# io-board-f-b.net
KiCad netlist of a schematic drawn in EAGLE
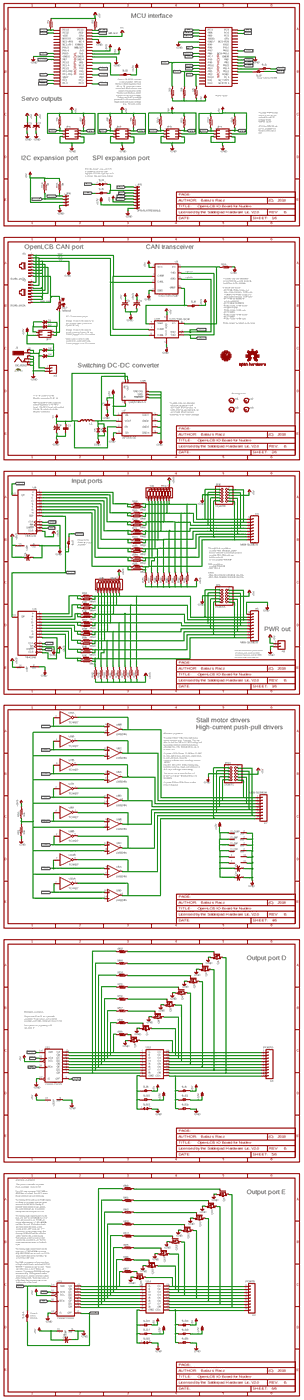
[diagram p0: schematic, sheet 1, overview]
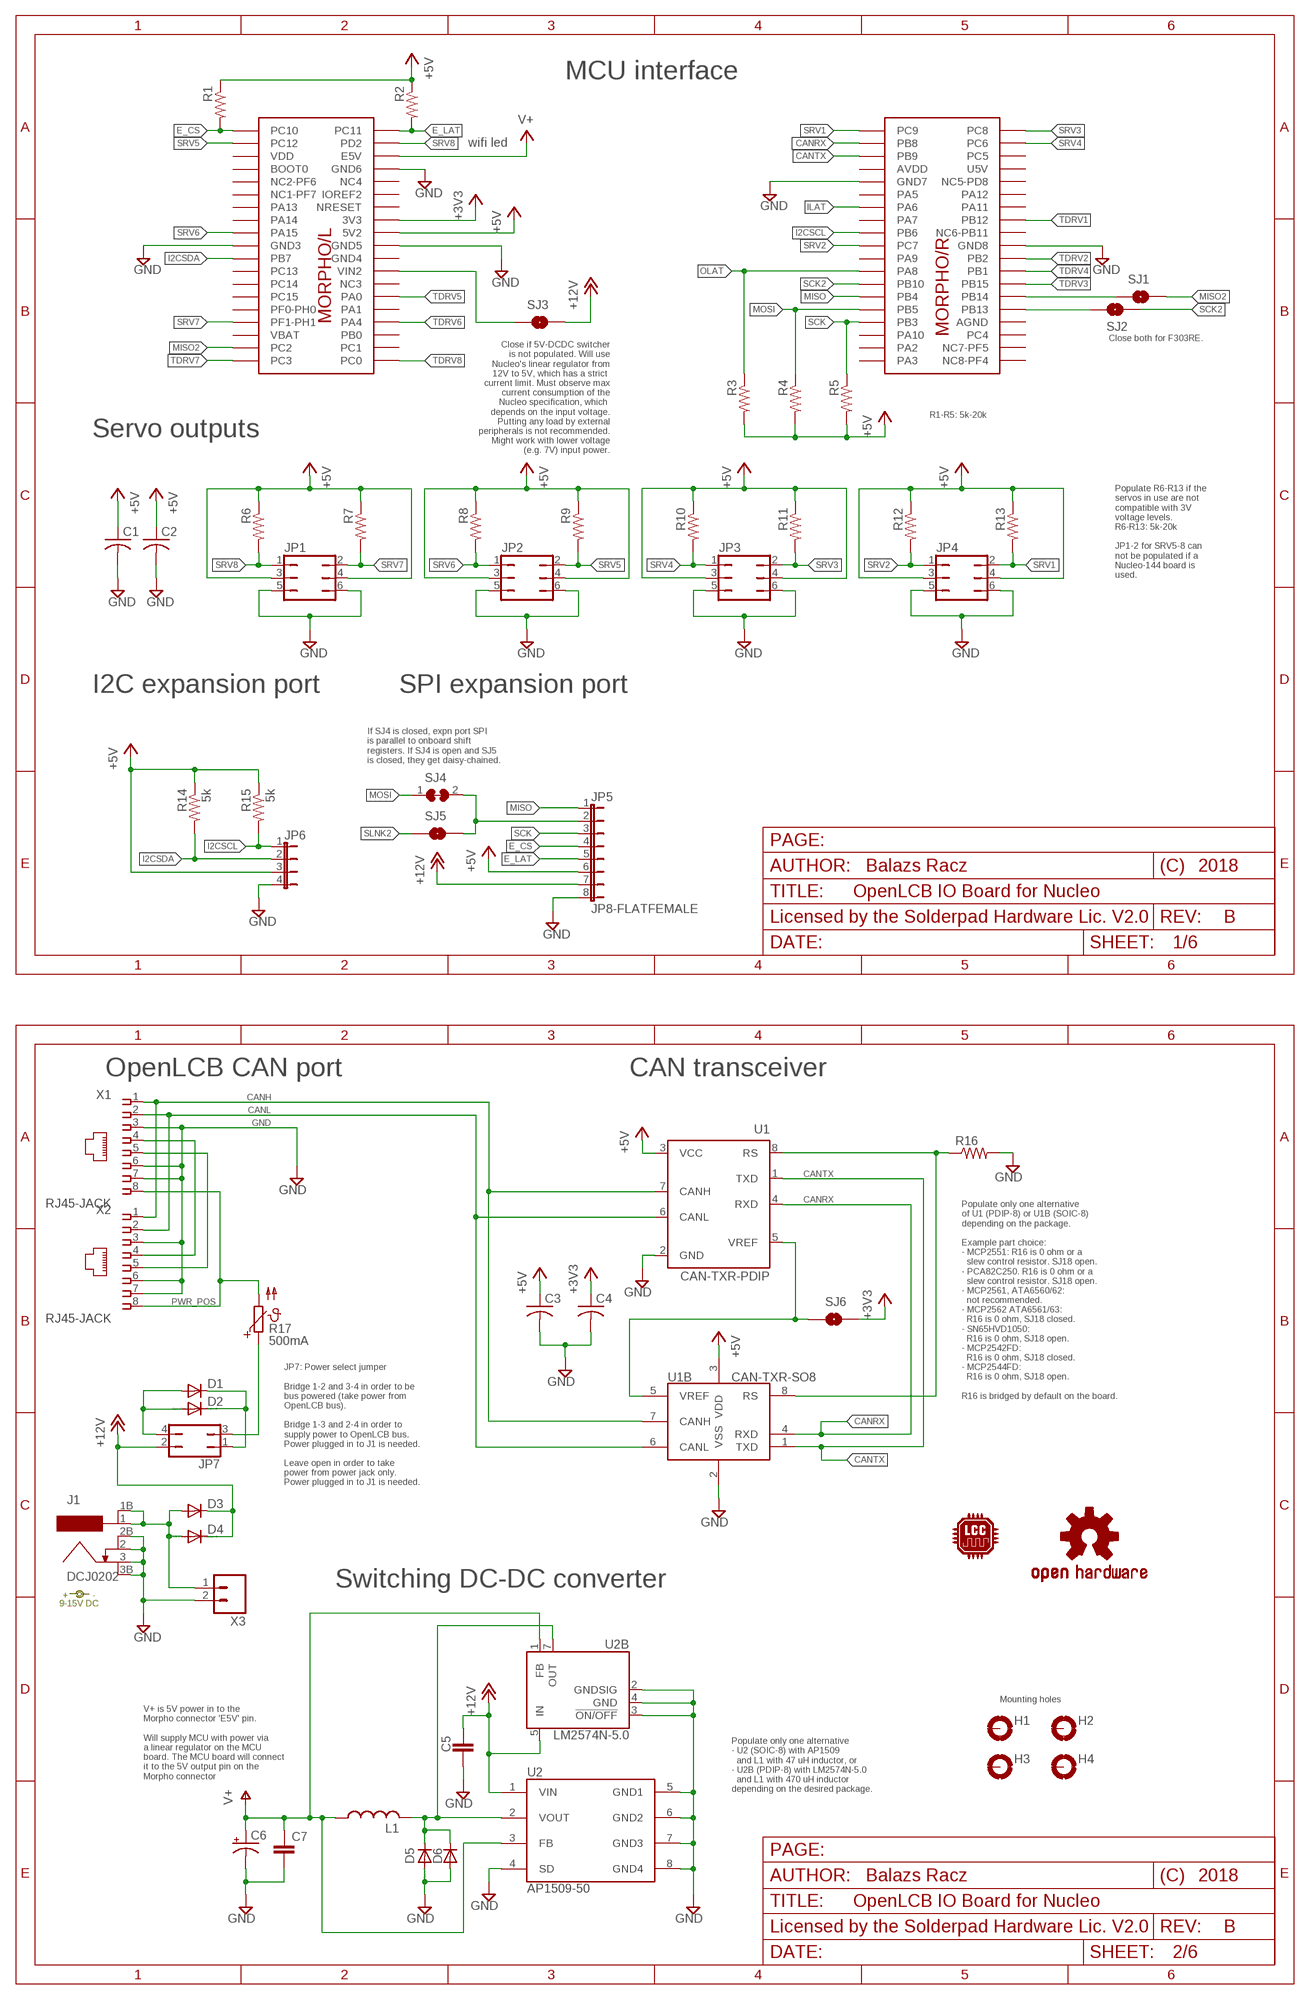
[diagram p1: schematic, sheet 1, part 1 of 4]
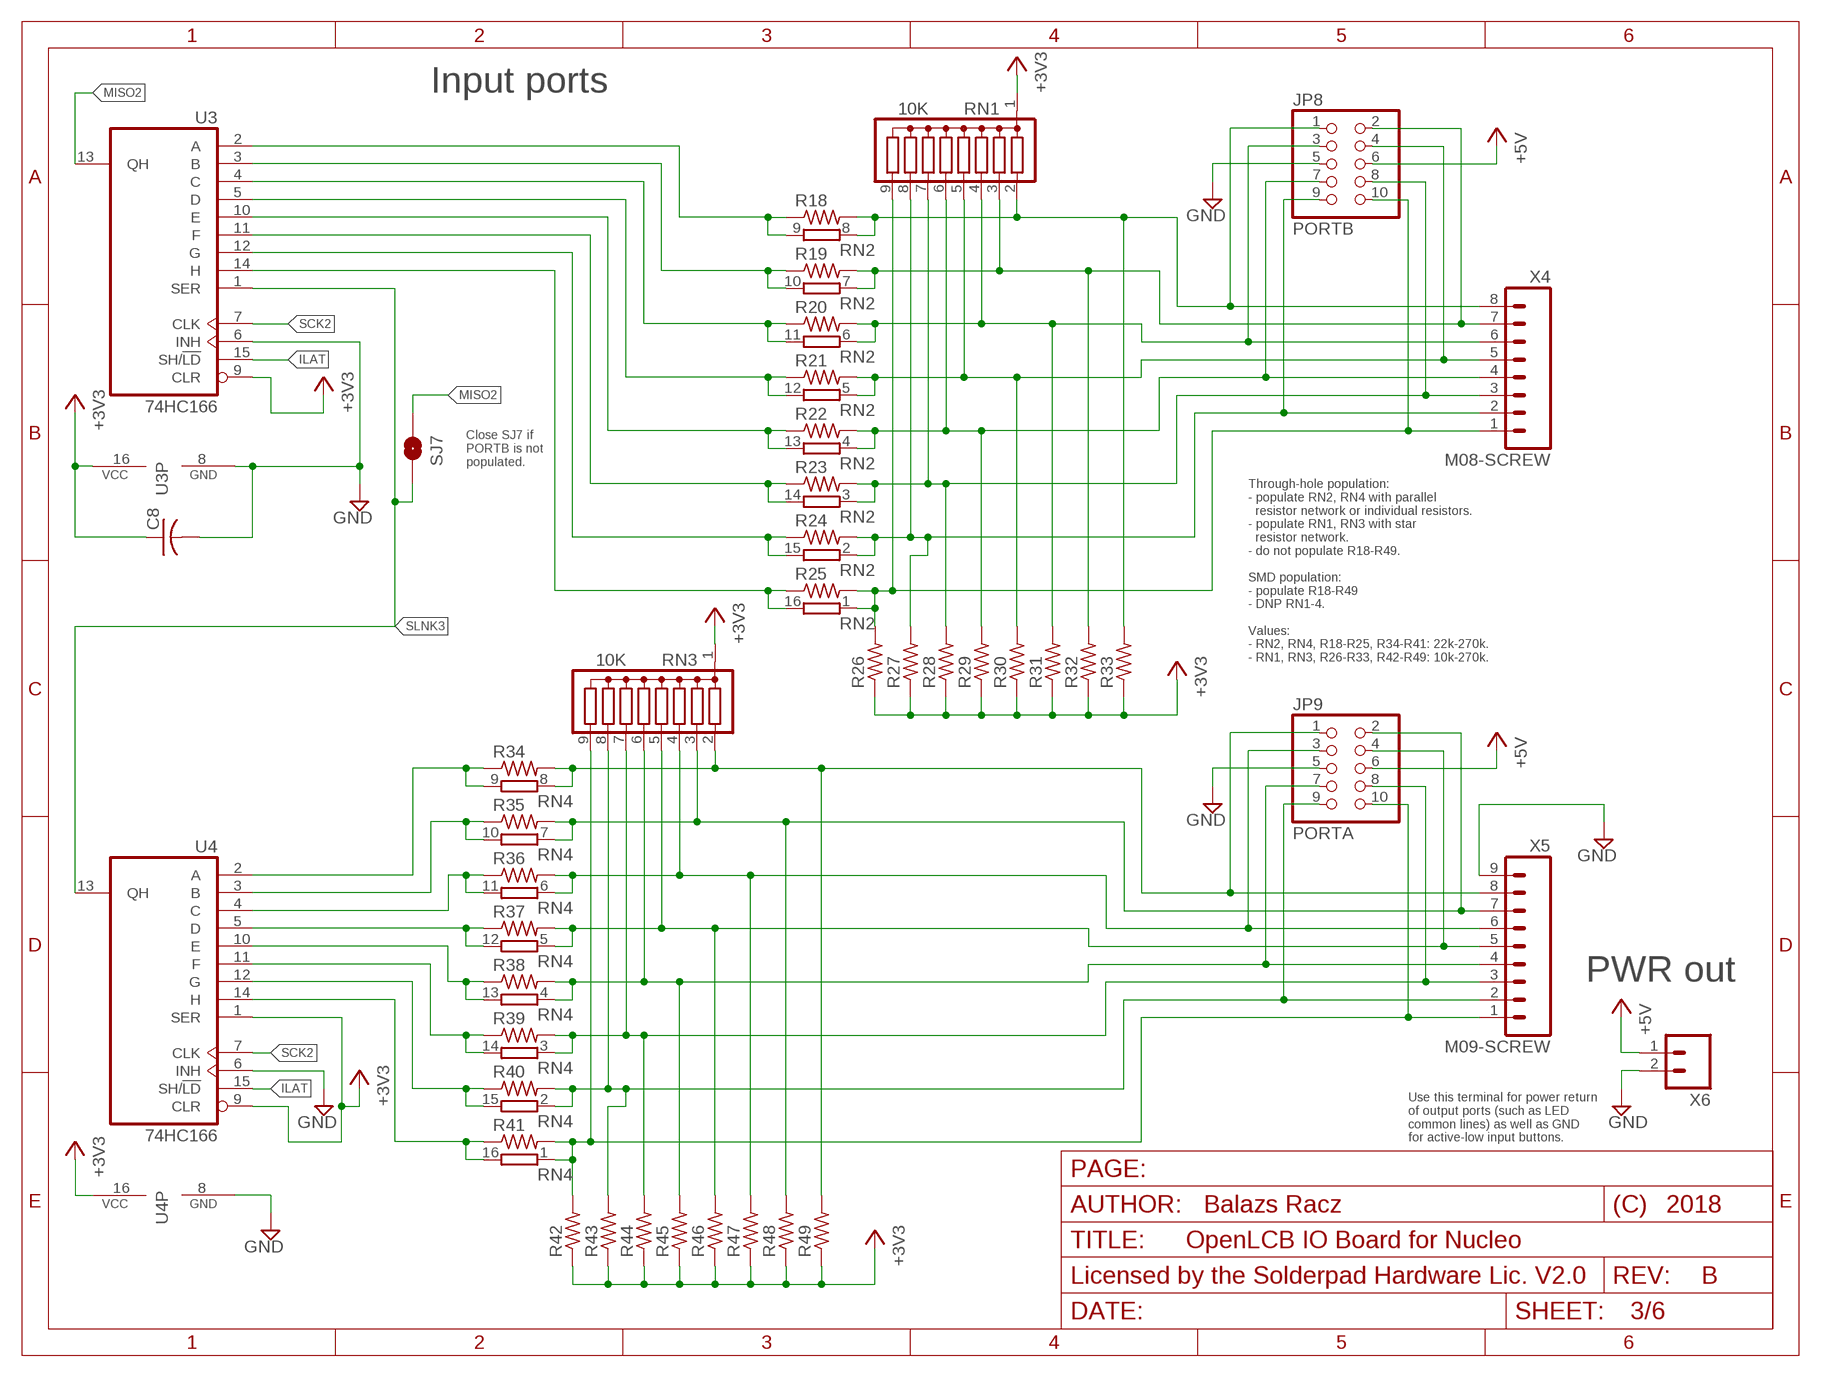
[diagram p2: schematic, sheet 1, part 2 of 4]
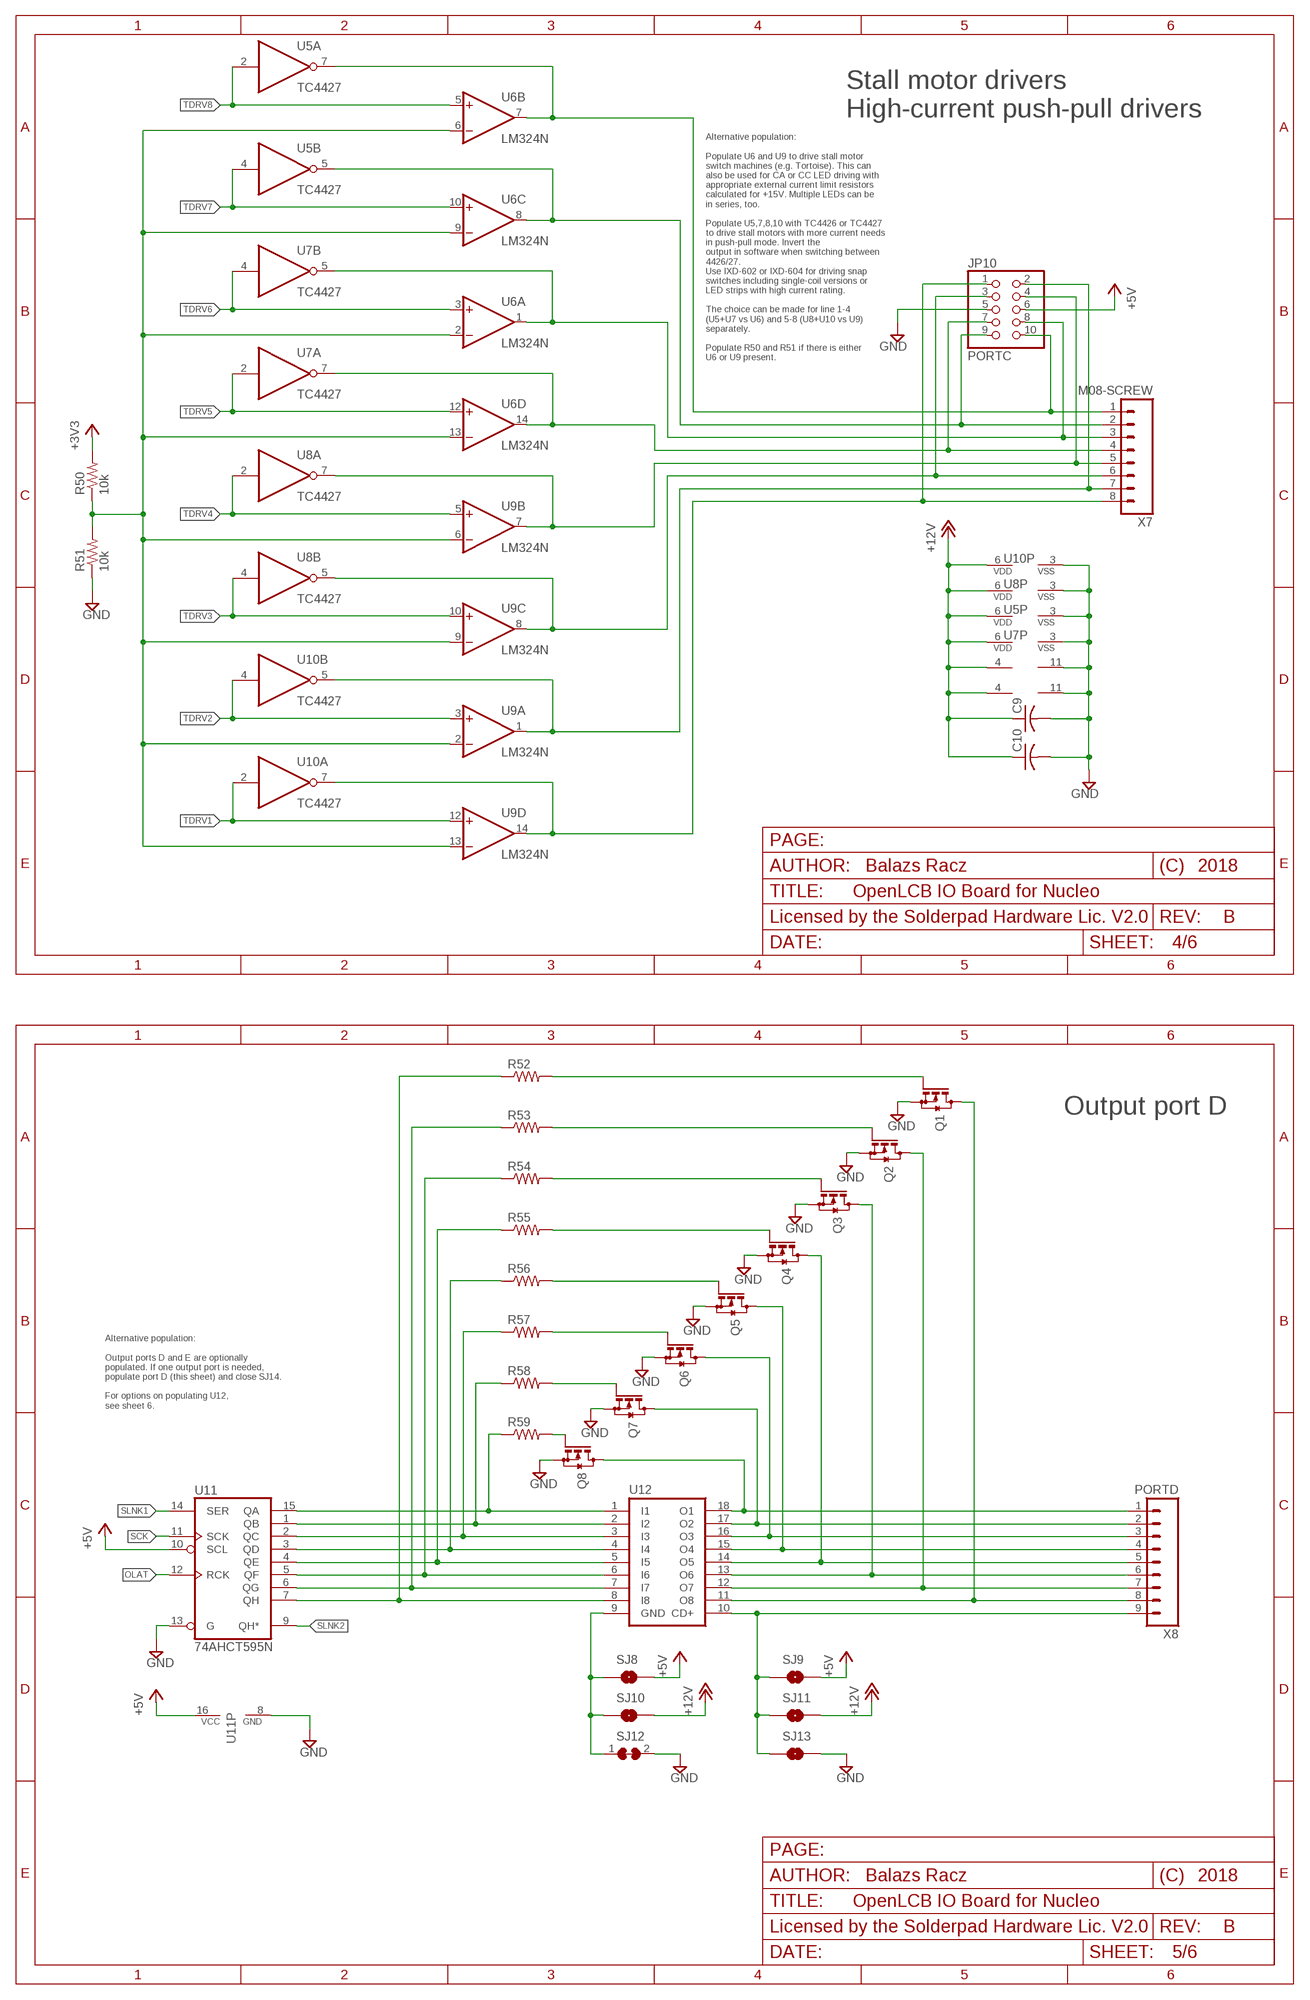
[diagram p3: schematic, sheet 1, part 3 of 4]
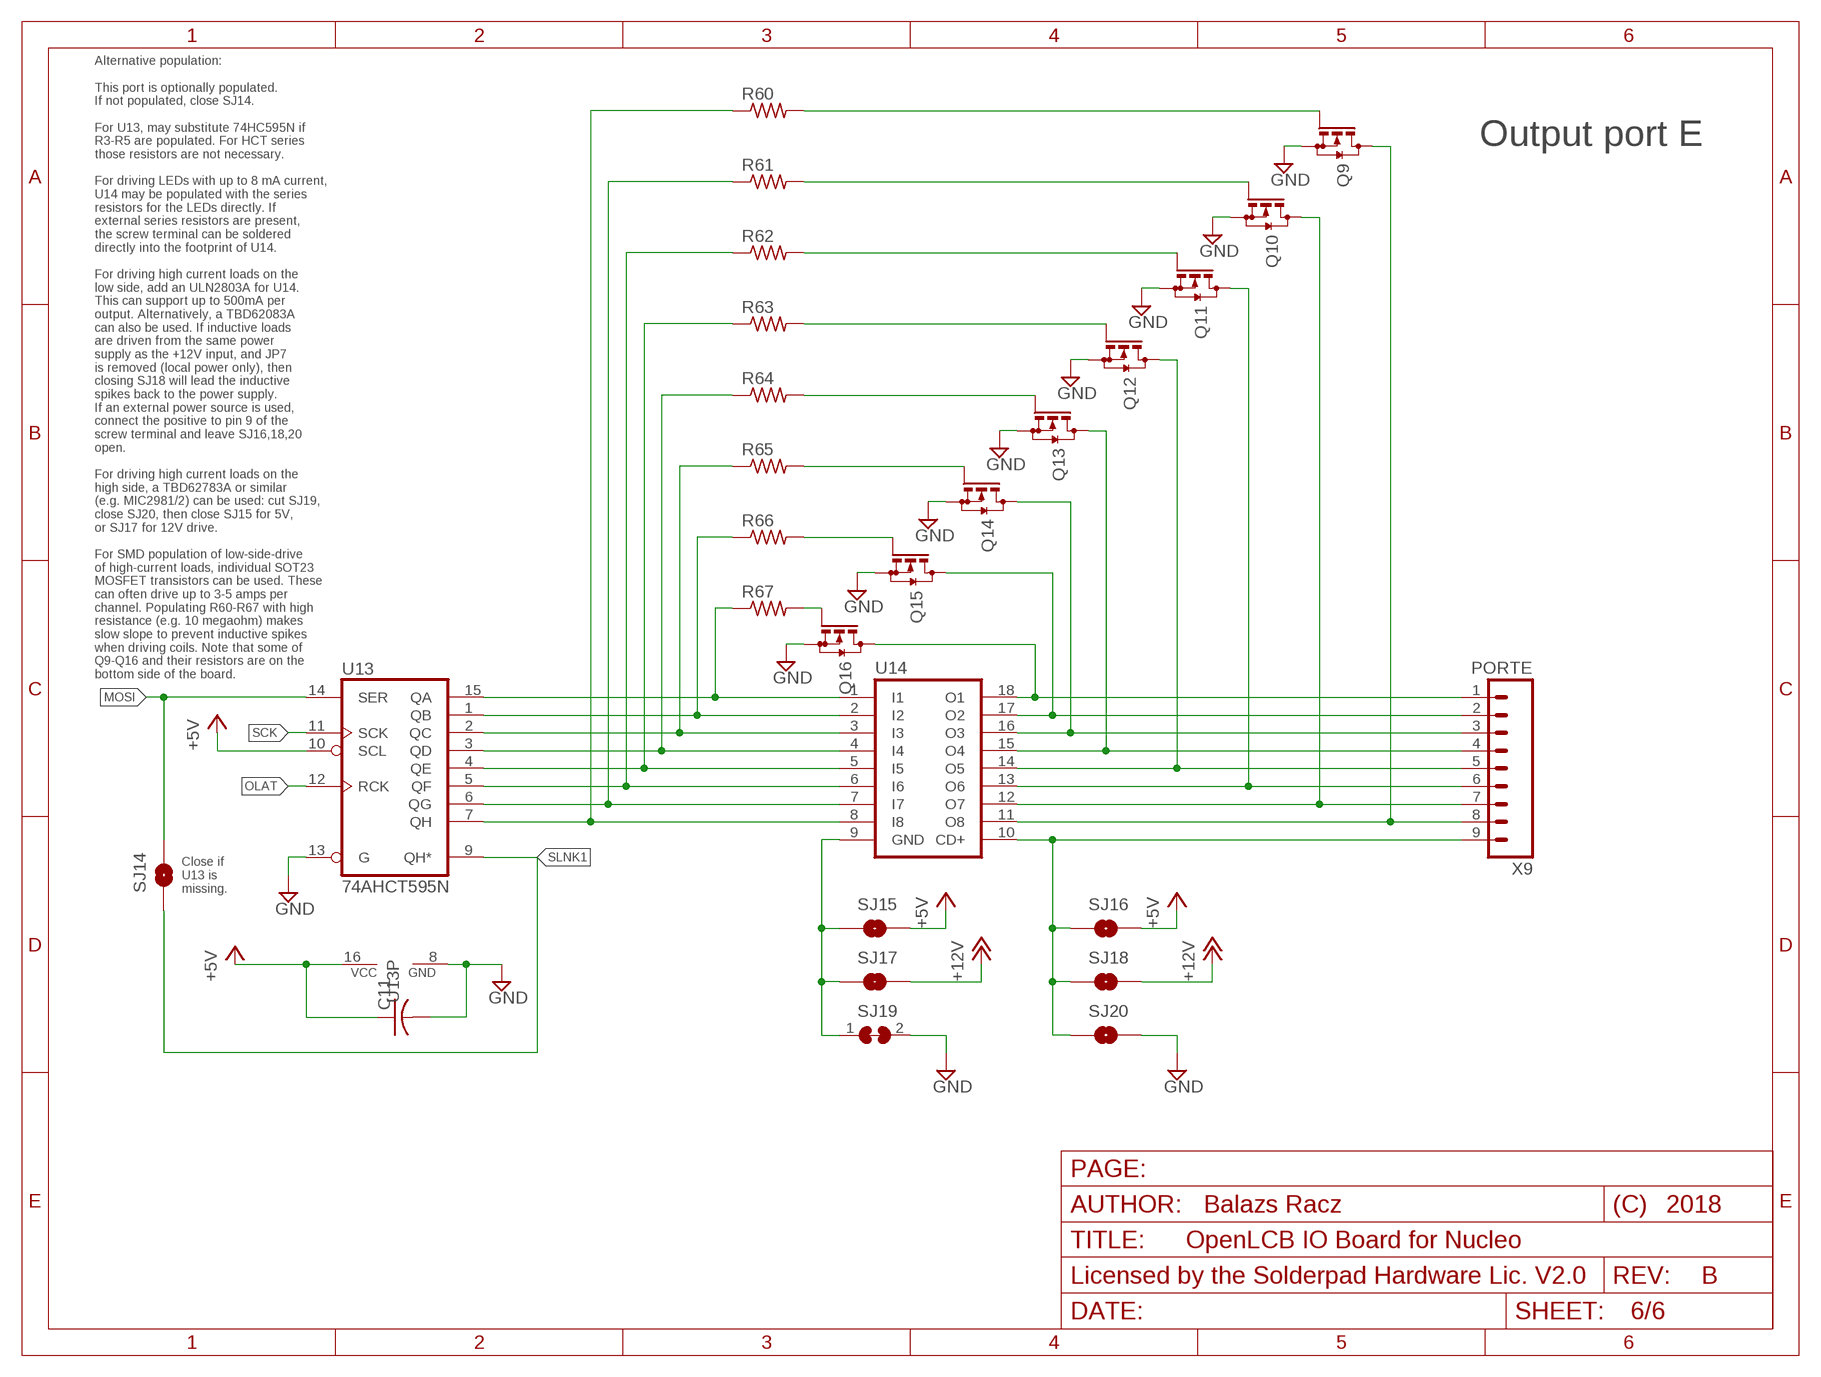
[diagram p4: schematic, sheet 1, part 4 of 4]

(export (version "E")
  (design (tool "Eeschema 10.0.6"))
  (components
    (comp (ref "C1")
      (value "C-USC1206")
      (footprint "eagle-import:C1206")
      (libsource (lib "eagle-import") (part "C-USC1206"))
    )
    (comp (ref "C2")
      (value "C-USC1206")
      (footprint "eagle-import:C1206")
      (libsource (lib "eagle-import") (part "C-USC1206"))
    )
    (comp (ref "C3")
      (value "C-USC0805")
      (footprint "eagle-import:C0805")
      (libsource (lib "eagle-import") (part "C-USC0805"))
    )
    (comp (ref "C4")
      (value "C-USC0805")
      (footprint "eagle-import:C0805")
      (libsource (lib "eagle-import") (part "C-USC0805"))
    )
    (comp (ref "C5")
      (value "C-EUC1206")
      (footprint "eagle-import:C1206")
      (libsource (lib "eagle-import") (part "C-EUC1206"))
    )
    (comp (ref "C6")
      (value "CPOL-USE2.5-5")
      (footprint "eagle-import:E2,5-5")
      (libsource (lib "eagle-import") (part "CPOL-USE2.5-5"))
    )
    (comp (ref "C7")
      (value "C-EUC1206")
      (footprint "eagle-import:C1206")
      (libsource (lib "eagle-import") (part "C-EUC1206"))
    )
    (comp (ref "C8")
      (value "C-USC0805")
      (footprint "eagle-import:C0805")
      (libsource (lib "eagle-import") (part "C-USC0805"))
    )
    (comp (ref "C9")
      (value "C-USC1206")
      (footprint "eagle-import:C1206")
      (libsource (lib "eagle-import") (part "C-USC1206"))
    )
    (comp (ref "C10")
      (value "C-USC1206")
      (footprint "eagle-import:C1206")
      (libsource (lib "eagle-import") (part "C-USC1206"))
    )
    (comp (ref "C11")
      (value "C-USC0805")
      (footprint "eagle-import:C0805")
      (libsource (lib "eagle-import") (part "C-USC0805"))
    )
    (comp (ref "D1")
      (value "DIODEDO-214AA-NODOC")
      (footprint "eagle-import:DO214AA-NODOC")
      (libsource (lib "eagle-import") (part "DIODEDO-214AA-NODOC"))
    )
    (comp (ref "D2")
      (value "DIODE-DO41-7.6")
      (footprint "eagle-import:DO41-7.6")
      (libsource (lib "eagle-import") (part "DIODE-DO41-7.6"))
    )
    (comp (ref "D3")
      (value "DIODEDO-214AA-NODOC")
      (footprint "eagle-import:DO214AA-NODOC")
      (libsource (lib "eagle-import") (part "DIODEDO-214AA-NODOC"))
    )
    (comp (ref "D4")
      (value "DIODE-DO41-7.6")
      (footprint "eagle-import:DO41-7.6")
      (libsource (lib "eagle-import") (part "DIODE-DO41-7.6"))
    )
    (comp (ref "D5")
      (value "DIODE-DO41-7.6")
      (footprint "eagle-import:DO41-7.6")
      (libsource (lib "eagle-import") (part "DIODE-DO41-7.6"))
    )
    (comp (ref "D6")
      (value "DIODEDO-214AA-NODOC")
      (footprint "eagle-import:DO214AA-NODOC")
      (libsource (lib "eagle-import") (part "DIODEDO-214AA-NODOC"))
    )
    (comp (ref "G1")
      (value "NUCLEO_64_GENERIC")
      (footprint "eagle-import:NUCLEO_BRD_BASE64")
      (libsource (lib "eagle-import") (part "NUCLEO_64_GENERIC"))
    )
    (comp (ref "H1")
      (value "MOUNT-PAD-ROUND3.3")
      (footprint "eagle-import:3,3-PAD")
      (libsource (lib "eagle-import") (part "MOUNT-PAD-ROUND3.3"))
    )
    (comp (ref "H2")
      (value "MOUNT-PAD-ROUND3.3")
      (footprint "eagle-import:3,3-PAD")
      (libsource (lib "eagle-import") (part "MOUNT-PAD-ROUND3.3"))
    )
    (comp (ref "H3")
      (value "MOUNT-PAD-ROUND3.3")
      (footprint "eagle-import:3,3-PAD")
      (libsource (lib "eagle-import") (part "MOUNT-PAD-ROUND3.3"))
    )
    (comp (ref "H4")
      (value "MOUNT-PAD-ROUND3.3")
      (footprint "eagle-import:3,3-PAD")
      (libsource (lib "eagle-import") (part "MOUNT-PAD-ROUND3.3"))
    )
    (comp (ref "J1")
      (value "DCJ0202")
      (footprint "eagle-import:DCJ0202")
      (libsource (lib "eagle-import") (part "DCJ0202"))
    )
    (comp (ref "JP1")
      (value "JP3Q")
      (footprint "eagle-import:JP3Q")
      (libsource (lib "eagle-import") (part "JP3Q"))
    )
    (comp (ref "JP2")
      (value "JP3Q")
      (footprint "eagle-import:JP3Q")
      (libsource (lib "eagle-import") (part "JP3Q"))
    )
    (comp (ref "JP3")
      (value "JP3Q")
      (footprint "eagle-import:JP3Q")
      (libsource (lib "eagle-import") (part "JP3Q"))
    )
    (comp (ref "JP4")
      (value "JP3Q")
      (footprint "eagle-import:JP3Q")
      (libsource (lib "eagle-import") (part "JP3Q"))
    )
    (comp (ref "JP5")
      (value "JP8-FLATFEMALE")
      (footprint "eagle-import:JP8F-FEM")
      (libsource (lib "eagle-import") (part "JP8-FLATFEMALE"))
    )
    (comp (ref "JP6")
      (value "JP4-FLAT")
      (footprint "eagle-import:JP4F")
      (libsource (lib "eagle-import") (part "JP4-FLAT"))
    )
    (comp (ref "JP7")
      (value "JP2Q")
      (footprint "eagle-import:JP2Q")
      (libsource (lib "eagle-import") (part "JP2Q"))
    )
    (comp (ref "JP8")
      (value "PORTB")
      (footprint "eagle-import:CON10M")
      (libsource (lib "eagle-import") (part "PINHD-2X5CN"))
    )
    (comp (ref "JP9")
      (value "PORTA")
      (footprint "eagle-import:CON10M")
      (libsource (lib "eagle-import") (part "PINHD-2X5CN"))
    )
    (comp (ref "JP10")
      (value "PORTC")
      (footprint "eagle-import:CON10M")
      (libsource (lib "eagle-import") (part "PINHD-2X5CN"))
    )
    (comp (ref "L1")
      (value "L-US")
      (footprint "eagle-import:L5-8,5")
      (libsource (lib "eagle-import") (part "L-US"))
    )
    (comp (ref "LG1")
      (value "LCC_LOGO")
      (footprint "eagle-import:LCC_LOGO")
      (libsource (lib "eagle-import") (part "LCC_LOGO"))
    )
    (comp (ref "LOGO1")
      (value "DOC-OSHW-LOGOM")
      (footprint "eagle-import:OSHW-LOGO-M")
      (libsource (lib "eagle-import") (part "DOC-OSHW-LOGOM"))
    )
    (comp (ref "P1")
      (value "9-15V DC")
      (footprint "eagle-import:POWER_USAGE")
      (libsource (lib "eagle-import") (part "DOC-POWER_LABEL"))
    )
    (comp (ref "Q1")
      (value "BSS123")
      (footprint "eagle-import:SOT23")
      (libsource (lib "eagle-import") (part "BSS123"))
    )
    (comp (ref "Q2")
      (value "BSS123")
      (footprint "eagle-import:SOT23")
      (libsource (lib "eagle-import") (part "BSS123"))
    )
    (comp (ref "Q3")
      (value "BSS123")
      (footprint "eagle-import:SOT23")
      (libsource (lib "eagle-import") (part "BSS123"))
    )
    (comp (ref "Q4")
      (value "BSS123")
      (footprint "eagle-import:SOT23")
      (libsource (lib "eagle-import") (part "BSS123"))
    )
    (comp (ref "Q5")
      (value "BSS123")
      (footprint "eagle-import:SOT23")
      (libsource (lib "eagle-import") (part "BSS123"))
    )
    (comp (ref "Q6")
      (value "BSS123")
      (footprint "eagle-import:SOT23")
      (libsource (lib "eagle-import") (part "BSS123"))
    )
    (comp (ref "Q7")
      (value "BSS123")
      (footprint "eagle-import:SOT23")
      (libsource (lib "eagle-import") (part "BSS123"))
    )
    (comp (ref "Q8")
      (value "BSS123")
      (footprint "eagle-import:SOT23")
      (libsource (lib "eagle-import") (part "BSS123"))
    )
    (comp (ref "Q9")
      (value "BSS123")
      (footprint "eagle-import:SOT23")
      (libsource (lib "eagle-import") (part "BSS123"))
    )
    (comp (ref "Q10")
      (value "BSS123")
      (footprint "eagle-import:SOT23")
      (libsource (lib "eagle-import") (part "BSS123"))
    )
    (comp (ref "Q11")
      (value "BSS123")
      (footprint "eagle-import:SOT23")
      (libsource (lib "eagle-import") (part "BSS123"))
    )
    (comp (ref "Q12")
      (value "BSS123")
      (footprint "eagle-import:SOT23")
      (libsource (lib "eagle-import") (part "BSS123"))
    )
    (comp (ref "Q13")
      (value "BSS123")
      (footprint "eagle-import:SOT23")
      (libsource (lib "eagle-import") (part "BSS123"))
    )
    (comp (ref "Q14")
      (value "BSS123")
      (footprint "eagle-import:SOT23")
      (libsource (lib "eagle-import") (part "BSS123"))
    )
    (comp (ref "Q15")
      (value "BSS123")
      (footprint "eagle-import:SOT23")
      (libsource (lib "eagle-import") (part "BSS123"))
    )
    (comp (ref "Q16")
      (value "BSS123")
      (footprint "eagle-import:SOT23")
      (libsource (lib "eagle-import") (part "BSS123"))
    )
    (comp (ref "R1")
      (value "R-US_R0805")
      (footprint "eagle-import:R0805")
      (libsource (lib "eagle-import") (part "rcl_334_R-US_R0805"))
    )
    (comp (ref "R2")
      (value "R-US_R0805")
      (footprint "eagle-import:R0805")
      (libsource (lib "eagle-import") (part "rcl_334_R-US_R0805"))
    )
    (comp (ref "R3")
      (value "R-US_R0805")
      (footprint "eagle-import:R0805")
      (libsource (lib "eagle-import") (part "rcl_334_R-US_R0805"))
    )
    (comp (ref "R4")
      (value "R-US_R0805")
      (footprint "eagle-import:R0805")
      (libsource (lib "eagle-import") (part "rcl_334_R-US_R0805"))
    )
    (comp (ref "R5")
      (value "R-US_R0805")
      (footprint "eagle-import:R0805")
      (libsource (lib "eagle-import") (part "rcl_334_R-US_R0805"))
    )
    (comp (ref "R6")
      (value "R-US_R0805")
      (footprint "eagle-import:R0805")
      (libsource (lib "eagle-import") (part "rcl_334_R-US_R0805"))
    )
    (comp (ref "R7")
      (value "R-US_R0805")
      (footprint "eagle-import:R0805")
      (libsource (lib "eagle-import") (part "rcl_334_R-US_R0805"))
    )
    (comp (ref "R8")
      (value "R-US_R0805")
      (footprint "eagle-import:R0805")
      (libsource (lib "eagle-import") (part "rcl_334_R-US_R0805"))
    )
    (comp (ref "R9")
      (value "R-US_R0805")
      (footprint "eagle-import:R0805")
      (libsource (lib "eagle-import") (part "rcl_334_R-US_R0805"))
    )
    (comp (ref "R10")
      (value "R-US_R0805")
      (footprint "eagle-import:R0805")
      (libsource (lib "eagle-import") (part "rcl_334_R-US_R0805"))
    )
    (comp (ref "R11")
      (value "R-US_R0805")
      (footprint "eagle-import:R0805")
      (libsource (lib "eagle-import") (part "rcl_334_R-US_R0805"))
    )
    (comp (ref "R12")
      (value "R-US_R0805")
      (footprint "eagle-import:R0805")
      (libsource (lib "eagle-import") (part "rcl_334_R-US_R0805"))
    )
    (comp (ref "R13")
      (value "R-US_R0805")
      (footprint "eagle-import:R0805")
      (libsource (lib "eagle-import") (part "rcl_334_R-US_R0805"))
    )
    (comp (ref "R14")
      (value "5k")
      (footprint "eagle-import:R0805")
      (libsource (lib "eagle-import") (part "rcl_334_R-US_R0805"))
    )
    (comp (ref "R15")
      (value "5k")
      (footprint "eagle-import:R0805")
      (libsource (lib "eagle-import") (part "rcl_334_R-US_R0805"))
    )
    (comp (ref "R16")
      (value "R-US_R0805")
      (footprint "eagle-import:R0805")
      (libsource (lib "eagle-import") (part "rcl_334_R-US_R0805"))
    )
    (comp (ref "R17")
      (value "500mA")
      (footprint "eagle-import:PTC1812")
      (libsource (lib "eagle-import") (part "PTC_1812"))
    )
    (comp (ref "R18")
      (value "R-US_R0603")
      (footprint "eagle-import:R0603")
      (libsource (lib "eagle-import") (part "rcl_334_R-US_R0603"))
    )
    (comp (ref "R19")
      (value "R-US_R0603")
      (footprint "eagle-import:R0603")
      (libsource (lib "eagle-import") (part "rcl_334_R-US_R0603"))
    )
    (comp (ref "R20")
      (value "R-US_R0603")
      (footprint "eagle-import:R0603")
      (libsource (lib "eagle-import") (part "rcl_334_R-US_R0603"))
    )
    (comp (ref "R21")
      (value "R-US_R0603")
      (footprint "eagle-import:R0603")
      (libsource (lib "eagle-import") (part "rcl_334_R-US_R0603"))
    )
    (comp (ref "R22")
      (value "R-US_R0603")
      (footprint "eagle-import:R0603")
      (libsource (lib "eagle-import") (part "rcl_334_R-US_R0603"))
    )
    (comp (ref "R23")
      (value "R-US_R0603")
      (footprint "eagle-import:R0603")
      (libsource (lib "eagle-import") (part "rcl_334_R-US_R0603"))
    )
    (comp (ref "R24")
      (value "R-US_R0603")
      (footprint "eagle-import:R0603")
      (libsource (lib "eagle-import") (part "rcl_334_R-US_R0603"))
    )
    (comp (ref "R25")
      (value "R-US_R0603")
      (footprint "eagle-import:R0603")
      (libsource (lib "eagle-import") (part "rcl_334_R-US_R0603"))
    )
    (comp (ref "R26")
      (value "R-US")
      (footprint "eagle-import:R0603")
      (libsource (lib "eagle-import") (part "R-US"))
    )
    (comp (ref "R27")
      (value "R-US")
      (footprint "eagle-import:R0603")
      (libsource (lib "eagle-import") (part "R-US"))
    )
    (comp (ref "R28")
      (value "R-US")
      (footprint "eagle-import:R0603")
      (libsource (lib "eagle-import") (part "R-US"))
    )
    (comp (ref "R29")
      (value "R-US")
      (footprint "eagle-import:R0603")
      (libsource (lib "eagle-import") (part "R-US"))
    )
    (comp (ref "R30")
      (value "R-US")
      (footprint "eagle-import:R0603")
      (libsource (lib "eagle-import") (part "R-US"))
    )
    (comp (ref "R31")
      (value "R-US")
      (footprint "eagle-import:R0603")
      (libsource (lib "eagle-import") (part "R-US"))
    )
    (comp (ref "R32")
      (value "R-US")
      (footprint "eagle-import:R0603")
      (libsource (lib "eagle-import") (part "R-US"))
    )
    (comp (ref "R33")
      (value "R-US")
      (footprint "eagle-import:R0603")
      (libsource (lib "eagle-import") (part "R-US"))
    )
    (comp (ref "R34")
      (value "R-US_R0603")
      (footprint "eagle-import:R0603")
      (libsource (lib "eagle-import") (part "rcl_334_R-US_R0603"))
    )
    (comp (ref "R35")
      (value "R-US_R0603")
      (footprint "eagle-import:R0603")
      (libsource (lib "eagle-import") (part "rcl_334_R-US_R0603"))
    )
    (comp (ref "R36")
      (value "R-US_R0603")
      (footprint "eagle-import:R0603")
      (libsource (lib "eagle-import") (part "rcl_334_R-US_R0603"))
    )
    (comp (ref "R37")
      (value "R-US_R0603")
      (footprint "eagle-import:R0603")
      (libsource (lib "eagle-import") (part "rcl_334_R-US_R0603"))
    )
    (comp (ref "R38")
      (value "R-US_R0603")
      (footprint "eagle-import:R0603")
      (libsource (lib "eagle-import") (part "rcl_334_R-US_R0603"))
    )
    (comp (ref "R39")
      (value "R-US_R0603")
      (footprint "eagle-import:R0603")
      (libsource (lib "eagle-import") (part "rcl_334_R-US_R0603"))
    )
    (comp (ref "R40")
      (value "R-US_R0603")
      (footprint "eagle-import:R0603")
      (libsource (lib "eagle-import") (part "rcl_334_R-US_R0603"))
    )
    (comp (ref "R41")
      (value "R-US_R0603")
      (footprint "eagle-import:R0603")
      (libsource (lib "eagle-import") (part "rcl_334_R-US_R0603"))
    )
    (comp (ref "R42")
      (value "R-US")
      (footprint "eagle-import:R0603")
      (libsource (lib "eagle-import") (part "R-US"))
    )
    (comp (ref "R43")
      (value "R-US")
      (footprint "eagle-import:R0603")
      (libsource (lib "eagle-import") (part "R-US"))
    )
    (comp (ref "R44")
      (value "R-US")
      (footprint "eagle-import:R0603")
      (libsource (lib "eagle-import") (part "R-US"))
    )
    (comp (ref "R45")
      (value "R-US")
      (footprint "eagle-import:R0603")
      (libsource (lib "eagle-import") (part "R-US"))
    )
    (comp (ref "R46")
      (value "R-US")
      (footprint "eagle-import:R0603")
      (libsource (lib "eagle-import") (part "R-US"))
    )
    (comp (ref "R47")
      (value "R-US")
      (footprint "eagle-import:R0603")
      (libsource (lib "eagle-import") (part "R-US"))
    )
    (comp (ref "R48")
      (value "R-US")
      (footprint "eagle-import:R0603")
      (libsource (lib "eagle-import") (part "R-US"))
    )
    (comp (ref "R49")
      (value "R-US")
      (footprint "eagle-import:R0603")
      (libsource (lib "eagle-import") (part "R-US"))
    )
    (comp (ref "R50")
      (value "10k")
      (footprint "eagle-import:R0805")
      (libsource (lib "eagle-import") (part "R-US_R0805"))
    )
    (comp (ref "R51")
      (value "10k")
      (footprint "eagle-import:R0805")
      (libsource (lib "eagle-import") (part "R-US_R0805"))
    )
    (comp (ref "R52")
      (value "R-US_R0603")
      (footprint "eagle-import:R0603")
      (libsource (lib "eagle-import") (part "R-US_R0603"))
    )
    (comp (ref "R53")
      (value "R-US_R0603")
      (footprint "eagle-import:R0603")
      (libsource (lib "eagle-import") (part "R-US_R0603"))
    )
    (comp (ref "R54")
      (value "R-US_R0603")
      (footprint "eagle-import:R0603")
      (libsource (lib "eagle-import") (part "R-US_R0603"))
    )
    (comp (ref "R55")
      (value "R-US_R0603")
      (footprint "eagle-import:R0603")
      (libsource (lib "eagle-import") (part "R-US_R0603"))
    )
    (comp (ref "R56")
      (value "R-US_R0603")
      (footprint "eagle-import:R0603")
      (libsource (lib "eagle-import") (part "R-US_R0603"))
    )
    (comp (ref "R57")
      (value "R-US_R0603")
      (footprint "eagle-import:R0603")
      (libsource (lib "eagle-import") (part "R-US_R0603"))
    )
    (comp (ref "R58")
      (value "R-US_R0603")
      (footprint "eagle-import:R0603")
      (libsource (lib "eagle-import") (part "R-US_R0603"))
    )
    (comp (ref "R59")
      (value "R-US_R0603")
      (footprint "eagle-import:R0603")
      (libsource (lib "eagle-import") (part "R-US_R0603"))
    )
    (comp (ref "R60")
      (value "R-US_R0603")
      (footprint "eagle-import:R0603")
      (libsource (lib "eagle-import") (part "R-US_R0603"))
    )
    (comp (ref "R61")
      (value "R-US_R0603")
      (footprint "eagle-import:R0603")
      (libsource (lib "eagle-import") (part "R-US_R0603"))
    )
    (comp (ref "R62")
      (value "R-US_R0603")
      (footprint "eagle-import:R0603")
      (libsource (lib "eagle-import") (part "R-US_R0603"))
    )
    (comp (ref "R63")
      (value "R-US_R0603")
      (footprint "eagle-import:R0603")
      (libsource (lib "eagle-import") (part "R-US_R0603"))
    )
    (comp (ref "R64")
      (value "R-US_R0603")
      (footprint "eagle-import:R0603")
      (libsource (lib "eagle-import") (part "R-US_R0603"))
    )
    (comp (ref "R65")
      (value "R-US_R0603")
      (footprint "eagle-import:R0603")
      (libsource (lib "eagle-import") (part "R-US_R0603"))
    )
    (comp (ref "R66")
      (value "R-US_R0603")
      (footprint "eagle-import:R0603")
      (libsource (lib "eagle-import") (part "R-US_R0603"))
    )
    (comp (ref "R67")
      (value "R-US_R0603")
      (footprint "eagle-import:R0603")
      (libsource (lib "eagle-import") (part "R-US_R0603"))
    )
    (comp (ref "RN1")
      (value "10K")
      (footprint "eagle-import:SIL9")
      (libsource (lib "eagle-import") (part "G08R"))
    )
    (comp (ref "RN2")
      (value "8R-P")
      (footprint "eagle-import:DIL16")
      (libsource (lib "eagle-import") (part "8R-P"))
    )
    (comp (ref "RN3")
      (value "10K")
      (footprint "eagle-import:SIL9")
      (libsource (lib "eagle-import") (part "G08R"))
    )
    (comp (ref "RN4")
      (value "8R-P")
      (footprint "eagle-import:DIL16")
      (libsource (lib "eagle-import") (part "8R-P"))
    )
    (comp (ref "SJ1")
      (value "SJRND2")
      (footprint "eagle-import:SJ_RND2")
      (libsource (lib "eagle-import") (part "SJRND2"))
    )
    (comp (ref "SJ2")
      (value "SJRND2")
      (footprint "eagle-import:SJ_RND2")
      (libsource (lib "eagle-import") (part "SJRND2"))
    )
    (comp (ref "SJ3")
      (value "SJRND2")
      (footprint "eagle-import:SJ_RND2")
      (libsource (lib "eagle-import") (part "SJRND2"))
    )
    (comp (ref "SJ4")
      (value "SJ-C")
      (footprint "eagle-import:SJW-C")
      (libsource (lib "eagle-import") (part "SJ-C"))
    )
    (comp (ref "SJ5")
      (value "SJRND2")
      (footprint "eagle-import:SJ_RND2")
      (libsource (lib "eagle-import") (part "SJRND2"))
    )
    (comp (ref "SJ6")
      (value "SJRND2")
      (footprint "eagle-import:SJ_RND2")
      (libsource (lib "eagle-import") (part "SJRND2"))
    )
    (comp (ref "SJ7")
      (value "SJRND2")
      (footprint "eagle-import:SJ_RND2")
      (libsource (lib "eagle-import") (part "SJRND2"))
    )
    (comp (ref "SJ8")
      (value "SJRND2")
      (footprint "eagle-import:SJ_RND2")
      (libsource (lib "eagle-import") (part "SJRND2"))
    )
    (comp (ref "SJ9")
      (value "SJRND2")
      (footprint "eagle-import:SJ_RND2")
      (libsource (lib "eagle-import") (part "SJRND2"))
    )
    (comp (ref "SJ10")
      (value "SJRND2")
      (footprint "eagle-import:SJ_RND2")
      (libsource (lib "eagle-import") (part "SJRND2"))
    )
    (comp (ref "SJ11")
      (value "SJRND2")
      (footprint "eagle-import:SJ_RND2")
      (libsource (lib "eagle-import") (part "SJRND2"))
    )
    (comp (ref "SJ12")
      (value "SJ-C")
      (footprint "eagle-import:SJW-C")
      (libsource (lib "eagle-import") (part "SJ-C"))
    )
    (comp (ref "SJ13")
      (value "SJRND2")
      (footprint "eagle-import:SJ_RND2")
      (libsource (lib "eagle-import") (part "SJRND2"))
    )
    (comp (ref "SJ14")
      (value "SJRND2")
      (footprint "eagle-import:SJ_RND2")
      (libsource (lib "eagle-import") (part "SJRND2"))
    )
    (comp (ref "SJ15")
      (value "SJRND2")
      (footprint "eagle-import:SJ_RND2")
      (libsource (lib "eagle-import") (part "SJRND2"))
    )
    (comp (ref "SJ16")
      (value "SJRND2")
      (footprint "eagle-import:SJ_RND2")
      (libsource (lib "eagle-import") (part "SJRND2"))
    )
    (comp (ref "SJ17")
      (value "SJRND2")
      (footprint "eagle-import:SJ_RND2")
      (libsource (lib "eagle-import") (part "SJRND2"))
    )
    (comp (ref "SJ18")
      (value "SJRND2")
      (footprint "eagle-import:SJ_RND2")
      (libsource (lib "eagle-import") (part "SJRND2"))
    )
    (comp (ref "SJ19")
      (value "SJ-C")
      (footprint "eagle-import:SJW-C")
      (libsource (lib "eagle-import") (part "SJ-C"))
    )
    (comp (ref "SJ20")
      (value "SJRND2")
      (footprint "eagle-import:SJ_RND2")
      (libsource (lib "eagle-import") (part "SJRND2"))
    )
    (comp (ref "U1")
      (value "CAN-TXR-PDIP")
      (footprint "eagle-import:DIL08")
      (libsource (lib "eagle-import") (part "PCA82C250"))
    )
    (comp (ref "U1B")
      (value "CAN-TXR-SO8")
      (footprint "eagle-import:SO-08")
      (libsource (lib "eagle-import") (part "MCP2551-SN"))
    )
    (comp (ref "U2")
      (value "AP1509-50")
      (footprint "eagle-import:SO-08")
      (libsource (lib "eagle-import") (part "AP1509"))
    )
    (comp (ref "U2B")
      (value "LM2574N-5.0")
      (footprint "eagle-import:DIL08")
      (libsource (lib "eagle-import") (part "LM2574?-N5.0"))
    )
    (comp (ref "U3")
      (value "74HC166")
      (footprint "eagle-import:DIL16")
      (libsource (lib "eagle-import") (part "74166N"))
    )
    (comp (ref "U4")
      (value "74HC166")
      (footprint "eagle-import:DIL16")
      (libsource (lib "eagle-import") (part "74166N"))
    )
    (comp (ref "U5")
      (value "TC4427")
      (footprint "eagle-import:DIL08-LONG")
      (libsource (lib "eagle-import") (part "TC4426APDIP"))
    )
    (comp (ref "U6")
      (value "LM324N")
      (footprint "eagle-import:DIL14")
      (libsource (lib "eagle-import") (part "LM324N"))
    )
    (comp (ref "U7")
      (value "TC4427")
      (footprint "eagle-import:DIL08-LONG")
      (libsource (lib "eagle-import") (part "TC4426APDIP"))
    )
    (comp (ref "U8")
      (value "TC4427")
      (footprint "eagle-import:DIL08-LONG")
      (libsource (lib "eagle-import") (part "TC4426APDIP"))
    )
    (comp (ref "U9")
      (value "LM324N")
      (footprint "eagle-import:DIL14")
      (libsource (lib "eagle-import") (part "LM324N"))
    )
    (comp (ref "U10")
      (value "TC4427")
      (footprint "eagle-import:DIL08-LONG")
      (libsource (lib "eagle-import") (part "TC4426APDIP"))
    )
    (comp (ref "U11")
      (value "74AHCT595N")
      (footprint "eagle-import:DIL16")
      (libsource (lib "eagle-import") (part "74595NHCT"))
    )
    (comp (ref "U12")
      (value "ULN2803A")
      (footprint "eagle-import:DIL18-THIN")
      (libsource (lib "eagle-import") (part "ULN2803A"))
    )
    (comp (ref "U13")
      (value "74AHCT595N")
      (footprint "eagle-import:DIL16")
      (libsource (lib "eagle-import") (part "74595NHCT"))
    )
    (comp (ref "U14")
      (value "ULN2803A")
      (footprint "eagle-import:DIL18-THIN")
      (libsource (lib "eagle-import") (part "ULN2803A"))
    )
    (comp (ref "X1")
      (value "RJ45-JACK")
      (footprint "eagle-import:RJ45-PULSE-E5J88")
      (libsource (lib "eagle-import") (part "RJ45-JACKRJ45-PULSE-E5J00"))
    )
    (comp (ref "X2")
      (value "RJ45-JACK")
      (footprint "eagle-import:RJ45-PULSE-E5J88")
      (libsource (lib "eagle-import") (part "RJ45-JACKRJ45-PULSE-E5J00"))
    )
    (comp (ref "X3")
      (value "CONNECTOR-M023.5MM-LOCK")
      (footprint "eagle-import:SCREWTERMINAL-3.5MM-2_LOCK")
      (libsource (lib "eagle-import") (part "CONNECTOR-M023.5MM-LOCK"))
    )
    (comp (ref "X4")
      (value "M08-SCREW")
      (footprint "eagle-import:1X08_TERMINAL")
      (libsource (lib "eagle-import") (part "M08-SCREW"))
    )
    (comp (ref "X5")
      (value "M09-SCREW")
      (footprint "eagle-import:1X09_TERMINAL")
      (libsource (lib "eagle-import") (part "M09-SCREW"))
    )
    (comp (ref "X6")
      (value "CONNECTOR-M023.5MM-LOCK")
      (footprint "eagle-import:SCREWTERMINAL-3.5MM-2_LOCK")
      (libsource (lib "eagle-import") (part "CONNECTOR-M023.5MM-LOCK"))
    )
    (comp (ref "X7")
      (value "M08-SCREW")
      (footprint "eagle-import:1X08_TERMINAL")
      (libsource (lib "eagle-import") (part "M08-SCREW"))
    )
    (comp (ref "X8")
      (value "PORTD")
      (footprint "eagle-import:1X09_TERMINAL")
      (libsource (lib "eagle-import") (part "M09-SCREW"))
    )
    (comp (ref "X9")
      (value "PORTE")
      (footprint "eagle-import:1X09_TERMINAL")
      (libsource (lib "eagle-import") (part "M09-SCREW"))
    )
  )
  (nets
    (net (code "1") (name "+3V3") (class "Default")
      (node (ref "C4") (pin "1") (pinfunction "1_1") (pintype "passive"))
      (node (ref "C8") (pin "1") (pinfunction "1_1") (pintype "passive"))
      (node (ref "G1") (pin "3V3") (pinfunction "3V3_3V3") (pintype "power_in"))
      (node (ref "R26") (pin "1") (pinfunction "1_1") (pintype "passive"))
      (node (ref "R27") (pin "1") (pinfunction "1_1") (pintype "passive"))
      (node (ref "R28") (pin "1") (pinfunction "1_1") (pintype "passive"))
      (node (ref "R29") (pin "1") (pinfunction "1_1") (pintype "passive"))
      (node (ref "R30") (pin "1") (pinfunction "1_1") (pintype "passive"))
      (node (ref "R31") (pin "1") (pinfunction "1_1") (pintype "passive"))
      (node (ref "R32") (pin "1") (pinfunction "1_1") (pintype "passive"))
      (node (ref "R33") (pin "1") (pinfunction "1_1") (pintype "passive"))
      (node (ref "R42") (pin "1") (pinfunction "1_1") (pintype "passive"))
      (node (ref "R43") (pin "1") (pinfunction "1_1") (pintype "passive"))
      (node (ref "R44") (pin "1") (pinfunction "1_1") (pintype "passive"))
      (node (ref "R45") (pin "1") (pinfunction "1_1") (pintype "passive"))
      (node (ref "R46") (pin "1") (pinfunction "1_1") (pintype "passive"))
      (node (ref "R47") (pin "1") (pinfunction "1_1") (pintype "passive"))
      (node (ref "R48") (pin "1") (pinfunction "1_1") (pintype "passive"))
      (node (ref "R49") (pin "1") (pinfunction "1_1") (pintype "passive"))
      (node (ref "R50") (pin "2") (pinfunction "2_2") (pintype "passive"))
      (node (ref "RN1") (pin "1") (pinfunction "1_1") (pintype "passive"))
      (node (ref "RN3") (pin "1") (pinfunction "1_1") (pintype "passive"))
      (node (ref "SJ6") (pin "P$1") (pinfunction "1_P$1") (pintype "passive"))
      (node (ref "U3") (pin "16") (pinfunction "VCC_16") (pintype "power_in"))
      (node (ref "U3") (pin "9") (pinfunction "CLR_9") (pintype "input"))
      (node (ref "U4") (pin "1") (pinfunction "SER_1") (pintype "input"))
      (node (ref "U4") (pin "16") (pinfunction "VCC_16") (pintype "power_in"))
      (node (ref "U4") (pin "9") (pinfunction "CLR_9") (pintype "input"))
    )
    (net (code "2") (name "+5V") (class "Default")
      (node (ref "C1") (pin "1") (pinfunction "1_1") (pintype "passive"))
      (node (ref "C11") (pin "1") (pinfunction "1_1") (pintype "passive"))
      (node (ref "C2") (pin "1") (pinfunction "1_1") (pintype "passive"))
      (node (ref "C3") (pin "1") (pinfunction "1_1") (pintype "passive"))
      (node (ref "G1") (pin "5V2") (pinfunction "5V2_5V2") (pintype "power_in"))
      (node (ref "JP1") (pin "3") (pinfunction "3_3") (pintype "passive"))
      (node (ref "JP1") (pin "4") (pinfunction "4_4") (pintype "passive"))
      (node (ref "JP10") (pin "6") (pinfunction "6_6") (pintype "passive"))
      (node (ref "JP2") (pin "3") (pinfunction "3_3") (pintype "passive"))
      (node (ref "JP2") (pin "4") (pinfunction "4_4") (pintype "passive"))
      (node (ref "JP3") (pin "3") (pinfunction "3_3") (pintype "passive"))
      (node (ref "JP3") (pin "4") (pinfunction "4_4") (pintype "passive"))
      (node (ref "JP4") (pin "3") (pinfunction "3_3") (pintype "passive"))
      (node (ref "JP4") (pin "4") (pinfunction "4_4") (pintype "passive"))
      (node (ref "JP5") (pin "6") (pinfunction "6_6") (pintype "passive"))
      (node (ref "JP6") (pin "3") (pinfunction "3_3") (pintype "passive"))
      (node (ref "JP8") (pin "6") (pinfunction "6_6") (pintype "passive"))
      (node (ref "JP9") (pin "6") (pinfunction "6_6") (pintype "passive"))
      (node (ref "R1") (pin "1") (pinfunction "1_1") (pintype "passive"))
      (node (ref "R10") (pin "1") (pinfunction "1_1") (pintype "passive"))
      (node (ref "R11") (pin "1") (pinfunction "1_1") (pintype "passive"))
      (node (ref "R12") (pin "1") (pinfunction "1_1") (pintype "passive"))
      (node (ref "R13") (pin "1") (pinfunction "1_1") (pintype "passive"))
      (node (ref "R14") (pin "1") (pinfunction "1_1") (pintype "passive"))
      (node (ref "R15") (pin "1") (pinfunction "1_1") (pintype "passive"))
      (node (ref "R2") (pin "1") (pinfunction "1_1") (pintype "passive"))
      (node (ref "R3") (pin "2") (pinfunction "2_2") (pintype "passive"))
      (node (ref "R4") (pin "2") (pinfunction "2_2") (pintype "passive"))
      (node (ref "R5") (pin "2") (pinfunction "2_2") (pintype "passive"))
      (node (ref "R6") (pin "1") (pinfunction "1_1") (pintype "passive"))
      (node (ref "R7") (pin "1") (pinfunction "1_1") (pintype "passive"))
      (node (ref "R8") (pin "1") (pinfunction "1_1") (pintype "passive"))
      (node (ref "R9") (pin "1") (pinfunction "1_1") (pintype "passive"))
      (node (ref "SJ15") (pin "P$2") (pinfunction "2_P$2") (pintype "passive"))
      (node (ref "SJ16") (pin "P$2") (pinfunction "2_P$2") (pintype "passive"))
      (node (ref "SJ8") (pin "P$2") (pinfunction "2_P$2") (pintype "passive"))
      (node (ref "SJ9") (pin "P$2") (pinfunction "2_P$2") (pintype "passive"))
      (node (ref "U1") (pin "3") (pinfunction "VCC_3") (pintype "power_in"))
      (node (ref "U11") (pin "10") (pinfunction "SCL_10") (pintype "input"))
      (node (ref "U11") (pin "16") (pinfunction "VCC_16") (pintype "power_in"))
      (node (ref "U13") (pin "10") (pinfunction "SCL_10") (pintype "input"))
      (node (ref "U13") (pin "16") (pinfunction "VCC_16") (pintype "power_in"))
      (node (ref "U1B") (pin "3") (pinfunction "VDD_3") (pintype "power_in"))
      (node (ref "X6") (pin "1") (pinfunction "1_1") (pintype "passive"))
    )
    (net (code "3") (name "+12V") (class "Default")
      (node (ref "C10") (pin "1") (pinfunction "1_1") (pintype "passive"))
      (node (ref "C5") (pin "1") (pinfunction "1_1") (pintype "passive"))
      (node (ref "C9") (pin "1") (pinfunction "1_1") (pintype "passive"))
      (node (ref "D3") (pin "C") (pinfunction "C_C") (pintype "passive"))
      (node (ref "D4") (pin "C") (pinfunction "C_C") (pintype "passive"))
      (node (ref "JP5") (pin "7") (pinfunction "7_7") (pintype "passive"))
      (node (ref "JP7") (pin "2") (pinfunction "2_2") (pintype "passive"))
      (node (ref "SJ10") (pin "P$2") (pinfunction "2_P$2") (pintype "passive"))
      (node (ref "SJ11") (pin "P$2") (pinfunction "2_P$2") (pintype "passive"))
      (node (ref "SJ17") (pin "P$2") (pinfunction "2_P$2") (pintype "passive"))
      (node (ref "SJ18") (pin "P$2") (pinfunction "2_P$2") (pintype "passive"))
      (node (ref "SJ3") (pin "P$2") (pinfunction "2_P$2") (pintype "passive"))
      (node (ref "U10") (pin "6") (pinfunction "VDD_6") (pintype "power_in"))
      (node (ref "U2") (pin "1") (pinfunction "VIN_1") (pintype "bidirectional"))
      (node (ref "U2B") (pin "5") (pinfunction "IN_5") (pintype "input"))
      (node (ref "U5") (pin "6") (pinfunction "VDD_6") (pintype "power_in"))
      (node (ref "U6") (pin "4") (pinfunction "V+_4") (pintype "power_in"))
      (node (ref "U7") (pin "6") (pinfunction "VDD_6") (pintype "power_in"))
      (node (ref "U8") (pin "6") (pinfunction "VDD_6") (pintype "power_in"))
      (node (ref "U9") (pin "4") (pinfunction "V+_4") (pintype "power_in"))
    )
    (net (code "4") (name "/AGND") (class "Default")
      (node (ref "G1") (pin "AGND") (pinfunction "AGND_AGND") (pintype "power_in"))
    )
    (net (code "5") (name "/AVDD") (class "Default")
      (node (ref "G1") (pin "AVDD") (pinfunction "AVDD_AVDD") (pintype "power_in"))
    )
    (net (code "6") (name "/CANH") (class "Default")
      (node (ref "U1") (pin "7") (pinfunction "CANH_7") (pintype "bidirectional"))
      (node (ref "U1B") (pin "7") (pinfunction "CANH_7") (pintype "bidirectional"))
      (node (ref "X1") (pin "1") (pinfunction "1_1") (pintype "passive"))
      (node (ref "X2") (pin "1") (pinfunction "1_1") (pintype "passive"))
    )
    (net (code "7") (name "/CANL") (class "Default")
      (node (ref "U1") (pin "6") (pinfunction "CANL_6") (pintype "bidirectional"))
      (node (ref "U1B") (pin "6") (pinfunction "CANL_6") (pintype "bidirectional"))
      (node (ref "X1") (pin "2") (pinfunction "2_2") (pintype "passive"))
      (node (ref "X2") (pin "2") (pinfunction "2_2") (pintype "passive"))
    )
    (net (code "8") (name "/GND4") (class "Default")
      (node (ref "G1") (pin "GND4") (pinfunction "GND4_GND4") (pintype "power_in"))
    )
    (net (code "9") (name "/PWR_POS") (class "Default")
      (node (ref "R17") (pin "2") (pinfunction "2_2") (pintype "passive"))
      (node (ref "X1") (pin "8") (pinfunction "8_8") (pintype "passive"))
      (node (ref "X2") (pin "8") (pinfunction "8_8") (pintype "passive"))
    )
    (net (code "10") (name "/U5V") (class "Default")
      (node (ref "G1") (pin "U5V") (pinfunction "U5V_U5V") (pintype "power_in"))
    )
    (net (code "11") (name "/VBAT") (class "Default")
      (node (ref "G1") (pin "VBAT") (pinfunction "VBAT_VBAT") (pintype "power_in"))
    )
    (net (code "12") (name "/VDD") (class "Default")
      (node (ref "G1") (pin "VDD") (pinfunction "VDD_VDD") (pintype "power_in"))
    )
    (net (code "13") (name "CANRX") (class "Default")
      (node (ref "G1") (pin "PB8") (pinfunction "PB8_PB8") (pintype "bidirectional"))
      (node (ref "U1") (pin "4") (pinfunction "RXD_4") (pintype "output"))
      (node (ref "U1B") (pin "4") (pinfunction "RXD_4") (pintype "bidirectional"))
    )
    (net (code "14") (name "CANTX") (class "Default")
      (node (ref "G1") (pin "PB9") (pinfunction "PB9_PB9") (pintype "bidirectional"))
      (node (ref "U1") (pin "1") (pinfunction "TXD_1") (pintype "input"))
      (node (ref "U1B") (pin "1") (pinfunction "TXD_1") (pintype "bidirectional"))
    )
    (net (code "15") (name "E_CS") (class "Default")
      (node (ref "G1") (pin "PC10") (pinfunction "PC10_PC10") (pintype "bidirectional"))
      (node (ref "JP5") (pin "4") (pinfunction "4_4") (pintype "passive"))
      (node (ref "R1") (pin "2") (pinfunction "2_2") (pintype "passive"))
    )
    (net (code "16") (name "E_LAT") (class "Default")
      (node (ref "G1") (pin "PC11") (pinfunction "PC11_PC11") (pintype "bidirectional"))
      (node (ref "JP5") (pin "5") (pinfunction "5_5") (pintype "passive"))
      (node (ref "R2") (pin "2") (pinfunction "2_2") (pintype "passive"))
    )
    (net (code "17") (name "GND") (class "Default")
      (node (ref "C1") (pin "2") (pinfunction "2_2") (pintype "passive"))
      (node (ref "C10") (pin "2") (pinfunction "2_2") (pintype "passive"))
      (node (ref "C11") (pin "2") (pinfunction "2_2") (pintype "passive"))
      (node (ref "C2") (pin "2") (pinfunction "2_2") (pintype "passive"))
      (node (ref "C3") (pin "2") (pinfunction "2_2") (pintype "passive"))
      (node (ref "C4") (pin "2") (pinfunction "2_2") (pintype "passive"))
      (node (ref "C5") (pin "2") (pinfunction "2_2") (pintype "passive"))
      (node (ref "C6") (pin "-") (pinfunction "-_-") (pintype "passive"))
      (node (ref "C7") (pin "2") (pinfunction "2_2") (pintype "passive"))
      (node (ref "C8") (pin "2") (pinfunction "2_2") (pintype "passive"))
      (node (ref "C9") (pin "2") (pinfunction "2_2") (pintype "passive"))
      (node (ref "D5") (pin "A") (pinfunction "A_A") (pintype "passive"))
      (node (ref "D6") (pin "A") (pinfunction "A_A") (pintype "passive"))
      (node (ref "G1") (pin "GND3") (pinfunction "GND3_GND3") (pintype "power_in"))
      (node (ref "G1") (pin "GND5") (pinfunction "GND5_GND5") (pintype "power_in"))
      (node (ref "G1") (pin "GND6") (pinfunction "GND6_GND6") (pintype "power_in"))
      (node (ref "G1") (pin "GND7") (pinfunction "GND7_GND7") (pintype "power_in"))
      (node (ref "G1") (pin "GND8") (pinfunction "GND8_GND8") (pintype "power_in"))
      (node (ref "J1") (pin "2") (pinfunction "2_2") (pintype "passive"))
      (node (ref "J1") (pin "2B") (pinfunction "2B_2B") (pintype "passive"))
      (node (ref "J1") (pin "3") (pinfunction "3_3") (pintype "passive"))
      (node (ref "J1") (pin "3B") (pinfunction "3B_3B") (pintype "passive"))
      (node (ref "JP1") (pin "5") (pinfunction "5_5") (pintype "passive"))
      (node (ref "JP1") (pin "6") (pinfunction "6_6") (pintype "passive"))
      (node (ref "JP10") (pin "5") (pinfunction "5_5") (pintype "passive"))
      (node (ref "JP2") (pin "5") (pinfunction "5_5") (pintype "passive"))
      (node (ref "JP2") (pin "6") (pinfunction "6_6") (pintype "passive"))
      (node (ref "JP3") (pin "5") (pinfunction "5_5") (pintype "passive"))
      (node (ref "JP3") (pin "6") (pinfunction "6_6") (pintype "passive"))
      (node (ref "JP4") (pin "5") (pinfunction "5_5") (pintype "passive"))
      (node (ref "JP4") (pin "6") (pinfunction "6_6") (pintype "passive"))
      (node (ref "JP5") (pin "8") (pinfunction "8_8") (pintype "passive"))
      (node (ref "JP6") (pin "4") (pinfunction "4_4") (pintype "passive"))
      (node (ref "JP8") (pin "5") (pinfunction "5_5") (pintype "passive"))
      (node (ref "JP9") (pin "5") (pinfunction "5_5") (pintype "passive"))
      (node (ref "Q1") (pin "2") (pinfunction "S_2") (pintype "passive"))
      (node (ref "Q10") (pin "2") (pinfunction "S_2") (pintype "passive"))
      (node (ref "Q11") (pin "2") (pinfunction "S_2") (pintype "passive"))
      (node (ref "Q12") (pin "2") (pinfunction "S_2") (pintype "passive"))
      (node (ref "Q13") (pin "2") (pinfunction "S_2") (pintype "passive"))
      (node (ref "Q14") (pin "2") (pinfunction "S_2") (pintype "passive"))
      (node (ref "Q15") (pin "2") (pinfunction "S_2") (pintype "passive"))
      (node (ref "Q16") (pin "2") (pinfunction "S_2") (pintype "passive"))
      (node (ref "Q2") (pin "2") (pinfunction "S_2") (pintype "passive"))
      (node (ref "Q3") (pin "2") (pinfunction "S_2") (pintype "passive"))
      (node (ref "Q4") (pin "2") (pinfunction "S_2") (pintype "passive"))
      (node (ref "Q5") (pin "2") (pinfunction "S_2") (pintype "passive"))
      (node (ref "Q6") (pin "2") (pinfunction "S_2") (pintype "passive"))
      (node (ref "Q7") (pin "2") (pinfunction "S_2") (pintype "passive"))
      (node (ref "Q8") (pin "2") (pinfunction "S_2") (pintype "passive"))
      (node (ref "Q9") (pin "2") (pinfunction "S_2") (pintype "passive"))
      (node (ref "R16") (pin "2") (pinfunction "2_2") (pintype "passive"))
      (node (ref "R51") (pin "1") (pinfunction "1_1") (pintype "passive"))
      (node (ref "SJ12") (pin "2") (pinfunction "2_2") (pintype "passive"))
      (node (ref "SJ13") (pin "P$2") (pinfunction "2_P$2") (pintype "passive"))
      (node (ref "SJ19") (pin "2") (pinfunction "2_2") (pintype "passive"))
      (node (ref "SJ20") (pin "P$2") (pinfunction "2_P$2") (pintype "passive"))
      (node (ref "U1") (pin "2") (pinfunction "GND_2") (pintype "power_in"))
      (node (ref "U10") (pin "3") (pinfunction "VSS_3") (pintype "power_in"))
      (node (ref "U11") (pin "13") (pinfunction "G_13") (pintype "input"))
      (node (ref "U11") (pin "8") (pinfunction "GND_8") (pintype "power_in"))
      (node (ref "U13") (pin "13") (pinfunction "G_13") (pintype "input"))
      (node (ref "U13") (pin "8") (pinfunction "GND_8") (pintype "power_in"))
      (node (ref "U1B") (pin "2") (pinfunction "VSS_2") (pintype "power_in"))
      (node (ref "U2") (pin "4") (pinfunction "SD_4") (pintype "bidirectional"))
      (node (ref "U2") (pin "5") (pinfunction "GND1_5") (pintype "power_in"))
      (node (ref "U2") (pin "6") (pinfunction "GND2_6") (pintype "power_in"))
      (node (ref "U2") (pin "7") (pinfunction "GND3_7") (pintype "power_in"))
      (node (ref "U2") (pin "8") (pinfunction "GND4_8") (pintype "power_in"))
      (node (ref "U2B") (pin "2") (pinfunction "GNDSIG_2") (pintype "input"))
      (node (ref "U2B") (pin "3") (pinfunction "~{ON/OFF}_3") (pintype "input"))
      (node (ref "U2B") (pin "4") (pinfunction "GND_4") (pintype "power_in"))
      (node (ref "U3") (pin "6") (pinfunction "INH_6") (pintype "input"))
      (node (ref "U3") (pin "8") (pinfunction "GND_8") (pintype "power_in"))
      (node (ref "U4") (pin "6") (pinfunction "INH_6") (pintype "input"))
      (node (ref "U4") (pin "8") (pinfunction "GND_8") (pintype "power_in"))
      (node (ref "U5") (pin "3") (pinfunction "VSS_3") (pintype "power_in"))
      (node (ref "U6") (pin "11") (pinfunction "V-_11") (pintype "power_in"))
      (node (ref "U7") (pin "3") (pinfunction "VSS_3") (pintype "power_in"))
      (node (ref "U8") (pin "3") (pinfunction "VSS_3") (pintype "power_in"))
      (node (ref "U9") (pin "11") (pinfunction "V-_11") (pintype "power_in"))
      (node (ref "X1") (pin "3") (pinfunction "3_3") (pintype "passive"))
      (node (ref "X1") (pin "6") (pinfunction "6_6") (pintype "passive"))
      (node (ref "X1") (pin "7") (pinfunction "7_7") (pintype "passive"))
      (node (ref "X2") (pin "3") (pinfunction "3_3") (pintype "passive"))
      (node (ref "X2") (pin "6") (pinfunction "6_6") (pintype "passive"))
      (node (ref "X2") (pin "7") (pinfunction "7_7") (pintype "passive"))
      (node (ref "X3") (pin "2") (pinfunction "2_2") (pintype "passive"))
      (node (ref "X5") (pin "9") (pinfunction "9_9") (pintype "passive"))
      (node (ref "X6") (pin "2") (pinfunction "2_2") (pintype "passive"))
    )
    (net (code "18") (name "I2CSCL") (class "Default")
      (node (ref "G1") (pin "PB6") (pinfunction "PB6_PB6") (pintype "bidirectional"))
      (node (ref "JP6") (pin "1") (pinfunction "1_1") (pintype "passive"))
      (node (ref "R15") (pin "2") (pinfunction "2_2") (pintype "passive"))
    )
    (net (code "19") (name "I2CSDA") (class "Default")
      (node (ref "G1") (pin "PB7") (pinfunction "PB7_PB7") (pintype "bidirectional"))
      (node (ref "JP6") (pin "2") (pinfunction "2_2") (pintype "passive"))
      (node (ref "R14") (pin "2") (pinfunction "2_2") (pintype "passive"))
    )
    (net (code "20") (name "ILAT") (class "Default")
      (node (ref "G1") (pin "PA6") (pinfunction "PA6_PA6") (pintype "bidirectional"))
      (node (ref "U3") (pin "15") (pinfunction "SH/~{LD}_15") (pintype "input"))
      (node (ref "U4") (pin "15") (pinfunction "SH/~{LD}_15") (pintype "input"))
    )
    (net (code "21") (name "MISO") (class "Default")
      (node (ref "G1") (pin "PB4") (pinfunction "PB4_PB4") (pintype "bidirectional"))
      (node (ref "JP5") (pin "1") (pinfunction "1_1") (pintype "passive"))
    )
    (net (code "22") (name "MISO2") (class "Default")
      (node (ref "G1") (pin "PC2") (pinfunction "PC2_PC2") (pintype "bidirectional"))
      (node (ref "SJ1") (pin "P$2") (pinfunction "2_P$2") (pintype "passive"))
      (node (ref "SJ7") (pin "P$2") (pinfunction "2_P$2") (pintype "passive"))
      (node (ref "U3") (pin "13") (pinfunction "QH_13") (pintype "output"))
    )
    (net (code "23") (name "MOSI") (class "Default")
      (node (ref "G1") (pin "PB5") (pinfunction "PB5_PB5") (pintype "bidirectional"))
      (node (ref "R4") (pin "1") (pinfunction "1_1") (pintype "passive"))
      (node (ref "SJ14") (pin "P$2") (pinfunction "2_P$2") (pintype "passive"))
      (node (ref "SJ4") (pin "1") (pinfunction "1_1") (pintype "passive"))
      (node (ref "U13") (pin "14") (pinfunction "SER_14") (pintype "input"))
    )
    (net (code "24") (name "Net-(D1-PadA)") (class "Default")
      (node (ref "D1") (pin "A") (pinfunction "A_A") (pintype "passive"))
      (node (ref "D2") (pin "A") (pinfunction "A_A") (pintype "passive"))
      (node (ref "JP7") (pin "4") (pinfunction "4_4") (pintype "passive"))
    )
    (net (code "25") (name "Net-(D1-PadC)") (class "Default")
      (node (ref "D1") (pin "C") (pinfunction "C_C") (pintype "passive"))
      (node (ref "D2") (pin "C") (pinfunction "C_C") (pintype "passive"))
      (node (ref "JP7") (pin "1") (pinfunction "1_1") (pintype "passive"))
    )
    (net (code "26") (name "Net-(D3-PadA)") (class "Default")
      (node (ref "D3") (pin "A") (pinfunction "A_A") (pintype "passive"))
      (node (ref "D4") (pin "A") (pinfunction "A_A") (pintype "passive"))
      (node (ref "J1") (pin "1") (pinfunction "1_1") (pintype "passive"))
      (node (ref "J1") (pin "1B") (pinfunction "1B_1B") (pintype "passive"))
      (node (ref "X3") (pin "1") (pinfunction "1_1") (pintype "passive"))
    )
    (net (code "27") (name "Net-(JP7-Pad3)") (class "Default")
      (node (ref "JP7") (pin "3") (pinfunction "3_3") (pintype "passive"))
      (node (ref "R17") (pin "1") (pinfunction "1_1") (pintype "passive"))
    )
    (net (code "28") (name "Net-(JP8-Pad10)") (class "Default")
      (node (ref "JP8") (pin "10") (pinfunction "10_10") (pintype "passive"))
      (node (ref "R25") (pin "2") (pinfunction "2_2") (pintype "passive"))
      (node (ref "R26") (pin "2") (pinfunction "2_2") (pintype "passive"))
      (node (ref "RN1") (pin "9") (pinfunction "9_9") (pintype "passive"))
      (node (ref "RN2") (pin "1") (pinfunction "1_1") (pintype "passive"))
      (node (ref "X4") (pin "1") (pinfunction "1_1") (pintype "passive"))
    )
    (net (code "29") (name "Net-(JP9-Pad10)") (class "Default")
      (node (ref "JP9") (pin "10") (pinfunction "10_10") (pintype "passive"))
      (node (ref "R41") (pin "2") (pinfunction "2_2") (pintype "passive"))
      (node (ref "R42") (pin "2") (pinfunction "2_2") (pintype "passive"))
      (node (ref "RN3") (pin "9") (pinfunction "9_9") (pintype "passive"))
      (node (ref "RN4") (pin "1") (pinfunction "1_1") (pintype "passive"))
      (node (ref "X5") (pin "1") (pinfunction "1_1") (pintype "passive"))
    )
    (net (code "30") (name "Net-(Q1-D)") (class "Default")
      (node (ref "Q1") (pin "3") (pinfunction "D_3") (pintype "passive"))
      (node (ref "U12") (pin "11") (pinfunction "O8_11") (pintype "open_collector"))
      (node (ref "X8") (pin "8") (pinfunction "8_8") (pintype "passive"))
    )
    (net (code "31") (name "Net-(Q1-G)") (class "Default")
      (node (ref "Q1") (pin "1") (pinfunction "G_1") (pintype "passive"))
      (node (ref "R52") (pin "2") (pinfunction "2_2") (pintype "passive"))
    )
    (net (code "32") (name "Net-(Q2-D)") (class "Default")
      (node (ref "Q2") (pin "3") (pinfunction "D_3") (pintype "passive"))
      (node (ref "U12") (pin "12") (pinfunction "O7_12") (pintype "open_collector"))
      (node (ref "X8") (pin "7") (pinfunction "7_7") (pintype "passive"))
    )
    (net (code "33") (name "Net-(Q2-G)") (class "Default")
      (node (ref "Q2") (pin "1") (pinfunction "G_1") (pintype "passive"))
      (node (ref "R53") (pin "2") (pinfunction "2_2") (pintype "passive"))
    )
    (net (code "34") (name "Net-(Q3-D)") (class "Default")
      (node (ref "Q3") (pin "3") (pinfunction "D_3") (pintype "passive"))
      (node (ref "U12") (pin "13") (pinfunction "O6_13") (pintype "open_collector"))
      (node (ref "X8") (pin "6") (pinfunction "6_6") (pintype "passive"))
    )
    (net (code "35") (name "Net-(Q3-G)") (class "Default")
      (node (ref "Q3") (pin "1") (pinfunction "G_1") (pintype "passive"))
      (node (ref "R54") (pin "2") (pinfunction "2_2") (pintype "passive"))
    )
    (net (code "36") (name "Net-(Q4-D)") (class "Default")
      (node (ref "Q4") (pin "3") (pinfunction "D_3") (pintype "passive"))
      (node (ref "U12") (pin "14") (pinfunction "O5_14") (pintype "open_collector"))
      (node (ref "X8") (pin "5") (pinfunction "5_5") (pintype "passive"))
    )
    (net (code "37") (name "Net-(Q4-G)") (class "Default")
      (node (ref "Q4") (pin "1") (pinfunction "G_1") (pintype "passive"))
      (node (ref "R55") (pin "2") (pinfunction "2_2") (pintype "passive"))
    )
    (net (code "38") (name "Net-(Q5-D)") (class "Default")
      (node (ref "Q5") (pin "3") (pinfunction "D_3") (pintype "passive"))
      (node (ref "U12") (pin "15") (pinfunction "O4_15") (pintype "open_collector"))
      (node (ref "X8") (pin "4") (pinfunction "4_4") (pintype "passive"))
    )
    (net (code "39") (name "Net-(Q5-G)") (class "Default")
      (node (ref "Q5") (pin "1") (pinfunction "G_1") (pintype "passive"))
      (node (ref "R56") (pin "2") (pinfunction "2_2") (pintype "passive"))
    )
    (net (code "40") (name "Net-(Q6-D)") (class "Default")
      (node (ref "Q6") (pin "3") (pinfunction "D_3") (pintype "passive"))
      (node (ref "U12") (pin "16") (pinfunction "O3_16") (pintype "open_collector"))
      (node (ref "X8") (pin "3") (pinfunction "3_3") (pintype "passive"))
    )
    (net (code "41") (name "Net-(Q6-G)") (class "Default")
      (node (ref "Q6") (pin "1") (pinfunction "G_1") (pintype "passive"))
      (node (ref "R57") (pin "2") (pinfunction "2_2") (pintype "passive"))
    )
    (net (code "42") (name "Net-(Q7-D)") (class "Default")
      (node (ref "Q7") (pin "3") (pinfunction "D_3") (pintype "passive"))
      (node (ref "U12") (pin "17") (pinfunction "O2_17") (pintype "open_collector"))
      (node (ref "X8") (pin "2") (pinfunction "2_2") (pintype "passive"))
    )
    (net (code "43") (name "Net-(Q7-G)") (class "Default")
      (node (ref "Q7") (pin "1") (pinfunction "G_1") (pintype "passive"))
      (node (ref "R58") (pin "2") (pinfunction "2_2") (pintype "passive"))
    )
    (net (code "44") (name "Net-(Q8-D)") (class "Default")
      (node (ref "Q8") (pin "3") (pinfunction "D_3") (pintype "passive"))
      (node (ref "U12") (pin "18") (pinfunction "O1_18") (pintype "open_collector"))
      (node (ref "X8") (pin "1") (pinfunction "1_1") (pintype "passive"))
    )
    (net (code "45") (name "Net-(Q8-G)") (class "Default")
      (node (ref "Q8") (pin "1") (pinfunction "G_1") (pintype "passive"))
      (node (ref "R59") (pin "2") (pinfunction "2_2") (pintype "passive"))
    )
    (net (code "46") (name "Net-(Q9-D)") (class "Default")
      (node (ref "Q9") (pin "3") (pinfunction "D_3") (pintype "passive"))
      (node (ref "U14") (pin "11") (pinfunction "O8_11") (pintype "open_collector"))
      (node (ref "X9") (pin "8") (pinfunction "8_8") (pintype "passive"))
    )
    (net (code "47") (name "Net-(Q9-G)") (class "Default")
      (node (ref "Q9") (pin "1") (pinfunction "G_1") (pintype "passive"))
      (node (ref "R60") (pin "2") (pinfunction "2_2") (pintype "passive"))
    )
    (net (code "48") (name "Net-(Q10-D)") (class "Default")
      (node (ref "Q10") (pin "3") (pinfunction "D_3") (pintype "passive"))
      (node (ref "U14") (pin "12") (pinfunction "O7_12") (pintype "open_collector"))
      (node (ref "X9") (pin "7") (pinfunction "7_7") (pintype "passive"))
    )
    (net (code "49") (name "Net-(Q10-G)") (class "Default")
      (node (ref "Q10") (pin "1") (pinfunction "G_1") (pintype "passive"))
      (node (ref "R61") (pin "2") (pinfunction "2_2") (pintype "passive"))
    )
    (net (code "50") (name "Net-(Q11-D)") (class "Default")
      (node (ref "Q11") (pin "3") (pinfunction "D_3") (pintype "passive"))
      (node (ref "U14") (pin "13") (pinfunction "O6_13") (pintype "open_collector"))
      (node (ref "X9") (pin "6") (pinfunction "6_6") (pintype "passive"))
    )
    (net (code "51") (name "Net-(Q11-G)") (class "Default")
      (node (ref "Q11") (pin "1") (pinfunction "G_1") (pintype "passive"))
      (node (ref "R62") (pin "2") (pinfunction "2_2") (pintype "passive"))
    )
    (net (code "52") (name "Net-(Q12-D)") (class "Default")
      (node (ref "Q12") (pin "3") (pinfunction "D_3") (pintype "passive"))
      (node (ref "U14") (pin "14") (pinfunction "O5_14") (pintype "open_collector"))
      (node (ref "X9") (pin "5") (pinfunction "5_5") (pintype "passive"))
    )
    (net (code "53") (name "Net-(Q12-G)") (class "Default")
      (node (ref "Q12") (pin "1") (pinfunction "G_1") (pintype "passive"))
      (node (ref "R63") (pin "2") (pinfunction "2_2") (pintype "passive"))
    )
    (net (code "54") (name "Net-(Q13-D)") (class "Default")
      (node (ref "Q13") (pin "3") (pinfunction "D_3") (pintype "passive"))
      (node (ref "U14") (pin "15") (pinfunction "O4_15") (pintype "open_collector"))
      (node (ref "X9") (pin "4") (pinfunction "4_4") (pintype "passive"))
    )
    (net (code "55") (name "Net-(Q13-G)") (class "Default")
      (node (ref "Q13") (pin "1") (pinfunction "G_1") (pintype "passive"))
      (node (ref "R64") (pin "2") (pinfunction "2_2") (pintype "passive"))
    )
    (net (code "56") (name "Net-(Q14-D)") (class "Default")
      (node (ref "Q14") (pin "3") (pinfunction "D_3") (pintype "passive"))
      (node (ref "U14") (pin "16") (pinfunction "O3_16") (pintype "open_collector"))
      (node (ref "X9") (pin "3") (pinfunction "3_3") (pintype "passive"))
    )
    (net (code "57") (name "Net-(Q14-G)") (class "Default")
      (node (ref "Q14") (pin "1") (pinfunction "G_1") (pintype "passive"))
      (node (ref "R65") (pin "2") (pinfunction "2_2") (pintype "passive"))
    )
    (net (code "58") (name "Net-(Q15-D)") (class "Default")
      (node (ref "Q15") (pin "3") (pinfunction "D_3") (pintype "passive"))
      (node (ref "U14") (pin "17") (pinfunction "O2_17") (pintype "open_collector"))
      (node (ref "X9") (pin "2") (pinfunction "2_2") (pintype "passive"))
    )
    (net (code "59") (name "Net-(Q15-G)") (class "Default")
      (node (ref "Q15") (pin "1") (pinfunction "G_1") (pintype "passive"))
      (node (ref "R66") (pin "2") (pinfunction "2_2") (pintype "passive"))
    )
    (net (code "60") (name "Net-(Q16-D)") (class "Default")
      (node (ref "Q16") (pin "3") (pinfunction "D_3") (pintype "passive"))
      (node (ref "U14") (pin "18") (pinfunction "O1_18") (pintype "open_collector"))
      (node (ref "X9") (pin "1") (pinfunction "1_1") (pintype "passive"))
    )
    (net (code "61") (name "Net-(Q16-G)") (class "Default")
      (node (ref "Q16") (pin "1") (pinfunction "G_1") (pintype "passive"))
      (node (ref "R67") (pin "2") (pinfunction "2_2") (pintype "passive"))
    )
    (net (code "62") (name "Net-(RN2A-2)") (class "Default")
      (node (ref "R25") (pin "1") (pinfunction "1_1") (pintype "passive"))
      (node (ref "RN2") (pin "16") (pinfunction "2_16") (pintype "passive"))
      (node (ref "U3") (pin "14") (pinfunction "H_14") (pintype "input"))
    )
    (net (code "63") (name "Net-(RN2B-1)") (class "Default")
      (node (ref "JP8") (pin "9") (pinfunction "9_9") (pintype "passive"))
      (node (ref "R24") (pin "2") (pinfunction "2_2") (pintype "passive"))
      (node (ref "R27") (pin "2") (pinfunction "2_2") (pintype "passive"))
      (node (ref "RN1") (pin "8") (pinfunction "8_8") (pintype "passive"))
      (node (ref "RN2") (pin "2") (pinfunction "1_2") (pintype "passive"))
      (node (ref "X4") (pin "2") (pinfunction "2_2") (pintype "passive"))
    )
    (net (code "64") (name "Net-(RN2B-2)") (class "Default")
      (node (ref "R24") (pin "1") (pinfunction "1_1") (pintype "passive"))
      (node (ref "RN2") (pin "15") (pinfunction "2_15") (pintype "passive"))
      (node (ref "U3") (pin "12") (pinfunction "G_12") (pintype "input"))
    )
    (net (code "65") (name "Net-(RN2C-1)") (class "Default")
      (node (ref "JP8") (pin "8") (pinfunction "8_8") (pintype "passive"))
      (node (ref "R23") (pin "2") (pinfunction "2_2") (pintype "passive"))
      (node (ref "R28") (pin "2") (pinfunction "2_2") (pintype "passive"))
      (node (ref "RN1") (pin "7") (pinfunction "7_7") (pintype "passive"))
      (node (ref "RN2") (pin "3") (pinfunction "1_3") (pintype "passive"))
      (node (ref "X4") (pin "3") (pinfunction "3_3") (pintype "passive"))
    )
    (net (code "66") (name "Net-(RN2C-2)") (class "Default")
      (node (ref "R23") (pin "1") (pinfunction "1_1") (pintype "passive"))
      (node (ref "RN2") (pin "14") (pinfunction "2_14") (pintype "passive"))
      (node (ref "U3") (pin "11") (pinfunction "F_11") (pintype "input"))
    )
    (net (code "67") (name "Net-(RN2D-1)") (class "Default")
      (node (ref "JP8") (pin "7") (pinfunction "7_7") (pintype "passive"))
      (node (ref "R22") (pin "2") (pinfunction "2_2") (pintype "passive"))
      (node (ref "R29") (pin "2") (pinfunction "2_2") (pintype "passive"))
      (node (ref "RN1") (pin "6") (pinfunction "6_6") (pintype "passive"))
      (node (ref "RN2") (pin "4") (pinfunction "1_4") (pintype "passive"))
      (node (ref "X4") (pin "4") (pinfunction "4_4") (pintype "passive"))
    )
    (net (code "68") (name "Net-(RN2D-2)") (class "Default")
      (node (ref "R22") (pin "1") (pinfunction "1_1") (pintype "passive"))
      (node (ref "RN2") (pin "13") (pinfunction "2_13") (pintype "passive"))
      (node (ref "U3") (pin "10") (pinfunction "E_10") (pintype "input"))
    )
    (net (code "69") (name "Net-(RN2E-1)") (class "Default")
      (node (ref "JP8") (pin "4") (pinfunction "4_4") (pintype "passive"))
      (node (ref "R21") (pin "2") (pinfunction "2_2") (pintype "passive"))
      (node (ref "R30") (pin "2") (pinfunction "2_2") (pintype "passive"))
      (node (ref "RN1") (pin "5") (pinfunction "5_5") (pintype "passive"))
      (node (ref "RN2") (pin "5") (pinfunction "1_5") (pintype "passive"))
      (node (ref "X4") (pin "5") (pinfunction "5_5") (pintype "passive"))
    )
    (net (code "70") (name "Net-(RN2E-2)") (class "Default")
      (node (ref "R21") (pin "1") (pinfunction "1_1") (pintype "passive"))
      (node (ref "RN2") (pin "12") (pinfunction "2_12") (pintype "passive"))
      (node (ref "U3") (pin "5") (pinfunction "D_5") (pintype "input"))
    )
    (net (code "71") (name "Net-(RN2F-1)") (class "Default")
      (node (ref "JP8") (pin "3") (pinfunction "3_3") (pintype "passive"))
      (node (ref "R20") (pin "2") (pinfunction "2_2") (pintype "passive"))
      (node (ref "R31") (pin "2") (pinfunction "2_2") (pintype "passive"))
      (node (ref "RN1") (pin "4") (pinfunction "4_4") (pintype "passive"))
      (node (ref "RN2") (pin "6") (pinfunction "1_6") (pintype "passive"))
      (node (ref "X4") (pin "6") (pinfunction "6_6") (pintype "passive"))
    )
    (net (code "72") (name "Net-(RN2F-2)") (class "Default")
      (node (ref "R20") (pin "1") (pinfunction "1_1") (pintype "passive"))
      (node (ref "RN2") (pin "11") (pinfunction "2_11") (pintype "passive"))
      (node (ref "U3") (pin "4") (pinfunction "C_4") (pintype "input"))
    )
    (net (code "73") (name "Net-(RN2G-1)") (class "Default")
      (node (ref "JP8") (pin "2") (pinfunction "2_2") (pintype "passive"))
      (node (ref "R19") (pin "2") (pinfunction "2_2") (pintype "passive"))
      (node (ref "R32") (pin "2") (pinfunction "2_2") (pintype "passive"))
      (node (ref "RN1") (pin "3") (pinfunction "3_3") (pintype "passive"))
      (node (ref "RN2") (pin "7") (pinfunction "1_7") (pintype "passive"))
      (node (ref "X4") (pin "7") (pinfunction "7_7") (pintype "passive"))
    )
    (net (code "74") (name "Net-(RN2G-2)") (class "Default")
      (node (ref "R19") (pin "1") (pinfunction "1_1") (pintype "passive"))
      (node (ref "RN2") (pin "10") (pinfunction "2_10") (pintype "passive"))
      (node (ref "U3") (pin "3") (pinfunction "B_3") (pintype "input"))
    )
    (net (code "75") (name "Net-(RN2H-1)") (class "Default")
      (node (ref "JP8") (pin "1") (pinfunction "1_1") (pintype "passive"))
      (node (ref "R18") (pin "2") (pinfunction "2_2") (pintype "passive"))
      (node (ref "R33") (pin "2") (pinfunction "2_2") (pintype "passive"))
      (node (ref "RN1") (pin "2") (pinfunction "2_2") (pintype "passive"))
      (node (ref "RN2") (pin "8") (pinfunction "1_8") (pintype "passive"))
      (node (ref "X4") (pin "8") (pinfunction "8_8") (pintype "passive"))
    )
    (net (code "76") (name "Net-(RN2H-2)") (class "Default")
      (node (ref "R18") (pin "1") (pinfunction "1_1") (pintype "passive"))
      (node (ref "RN2") (pin "9") (pinfunction "2_9") (pintype "passive"))
      (node (ref "U3") (pin "2") (pinfunction "A_2") (pintype "input"))
    )
    (net (code "77") (name "Net-(RN4A-2)") (class "Default")
      (node (ref "R41") (pin "1") (pinfunction "1_1") (pintype "passive"))
      (node (ref "RN4") (pin "16") (pinfunction "2_16") (pintype "passive"))
      (node (ref "U4") (pin "14") (pinfunction "H_14") (pintype "input"))
    )
    (net (code "78") (name "Net-(RN4B-1)") (class "Default")
      (node (ref "JP9") (pin "9") (pinfunction "9_9") (pintype "passive"))
      (node (ref "R40") (pin "2") (pinfunction "2_2") (pintype "passive"))
      (node (ref "R43") (pin "2") (pinfunction "2_2") (pintype "passive"))
      (node (ref "RN3") (pin "8") (pinfunction "8_8") (pintype "passive"))
      (node (ref "RN4") (pin "2") (pinfunction "1_2") (pintype "passive"))
      (node (ref "X5") (pin "2") (pinfunction "2_2") (pintype "passive"))
    )
    (net (code "79") (name "Net-(RN4B-2)") (class "Default")
      (node (ref "R40") (pin "1") (pinfunction "1_1") (pintype "passive"))
      (node (ref "RN4") (pin "15") (pinfunction "2_15") (pintype "passive"))
      (node (ref "U4") (pin "12") (pinfunction "G_12") (pintype "input"))
    )
    (net (code "80") (name "Net-(RN4C-1)") (class "Default")
      (node (ref "JP9") (pin "8") (pinfunction "8_8") (pintype "passive"))
      (node (ref "R39") (pin "2") (pinfunction "2_2") (pintype "passive"))
      (node (ref "R44") (pin "2") (pinfunction "2_2") (pintype "passive"))
      (node (ref "RN3") (pin "7") (pinfunction "7_7") (pintype "passive"))
      (node (ref "RN4") (pin "3") (pinfunction "1_3") (pintype "passive"))
      (node (ref "X5") (pin "3") (pinfunction "3_3") (pintype "passive"))
    )
    (net (code "81") (name "Net-(RN4C-2)") (class "Default")
      (node (ref "R39") (pin "1") (pinfunction "1_1") (pintype "passive"))
      (node (ref "RN4") (pin "14") (pinfunction "2_14") (pintype "passive"))
      (node (ref "U4") (pin "11") (pinfunction "F_11") (pintype "input"))
    )
    (net (code "82") (name "Net-(RN4D-1)") (class "Default")
      (node (ref "JP9") (pin "7") (pinfunction "7_7") (pintype "passive"))
      (node (ref "R38") (pin "2") (pinfunction "2_2") (pintype "passive"))
      (node (ref "R45") (pin "2") (pinfunction "2_2") (pintype "passive"))
      (node (ref "RN3") (pin "6") (pinfunction "6_6") (pintype "passive"))
      (node (ref "RN4") (pin "4") (pinfunction "1_4") (pintype "passive"))
      (node (ref "X5") (pin "4") (pinfunction "4_4") (pintype "passive"))
    )
    (net (code "83") (name "Net-(RN4D-2)") (class "Default")
      (node (ref "R38") (pin "1") (pinfunction "1_1") (pintype "passive"))
      (node (ref "RN4") (pin "13") (pinfunction "2_13") (pintype "passive"))
      (node (ref "U4") (pin "10") (pinfunction "E_10") (pintype "input"))
    )
    (net (code "84") (name "Net-(RN4E-1)") (class "Default")
      (node (ref "JP9") (pin "4") (pinfunction "4_4") (pintype "passive"))
      (node (ref "R37") (pin "2") (pinfunction "2_2") (pintype "passive"))
      (node (ref "R46") (pin "2") (pinfunction "2_2") (pintype "passive"))
      (node (ref "RN3") (pin "5") (pinfunction "5_5") (pintype "passive"))
      (node (ref "RN4") (pin "5") (pinfunction "1_5") (pintype "passive"))
      (node (ref "X5") (pin "5") (pinfunction "5_5") (pintype "passive"))
    )
    (net (code "85") (name "Net-(RN4E-2)") (class "Default")
      (node (ref "R37") (pin "1") (pinfunction "1_1") (pintype "passive"))
      (node (ref "RN4") (pin "12") (pinfunction "2_12") (pintype "passive"))
      (node (ref "U4") (pin "5") (pinfunction "D_5") (pintype "input"))
    )
    (net (code "86") (name "Net-(RN4F-1)") (class "Default")
      (node (ref "JP9") (pin "3") (pinfunction "3_3") (pintype "passive"))
      (node (ref "R36") (pin "2") (pinfunction "2_2") (pintype "passive"))
      (node (ref "R47") (pin "2") (pinfunction "2_2") (pintype "passive"))
      (node (ref "RN3") (pin "4") (pinfunction "4_4") (pintype "passive"))
      (node (ref "RN4") (pin "6") (pinfunction "1_6") (pintype "passive"))
      (node (ref "X5") (pin "6") (pinfunction "6_6") (pintype "passive"))
    )
    (net (code "87") (name "Net-(RN4F-2)") (class "Default")
      (node (ref "R36") (pin "1") (pinfunction "1_1") (pintype "passive"))
      (node (ref "RN4") (pin "11") (pinfunction "2_11") (pintype "passive"))
      (node (ref "U4") (pin "4") (pinfunction "C_4") (pintype "input"))
    )
    (net (code "88") (name "Net-(RN4G-1)") (class "Default")
      (node (ref "JP9") (pin "2") (pinfunction "2_2") (pintype "passive"))
      (node (ref "R35") (pin "2") (pinfunction "2_2") (pintype "passive"))
      (node (ref "R48") (pin "2") (pinfunction "2_2") (pintype "passive"))
      (node (ref "RN3") (pin "3") (pinfunction "3_3") (pintype "passive"))
      (node (ref "RN4") (pin "7") (pinfunction "1_7") (pintype "passive"))
      (node (ref "X5") (pin "7") (pinfunction "7_7") (pintype "passive"))
    )
    (net (code "89") (name "Net-(RN4G-2)") (class "Default")
      (node (ref "R35") (pin "1") (pinfunction "1_1") (pintype "passive"))
      (node (ref "RN4") (pin "10") (pinfunction "2_10") (pintype "passive"))
      (node (ref "U4") (pin "3") (pinfunction "B_3") (pintype "input"))
    )
    (net (code "90") (name "Net-(RN4H-1)") (class "Default")
      (node (ref "JP9") (pin "1") (pinfunction "1_1") (pintype "passive"))
      (node (ref "R34") (pin "2") (pinfunction "2_2") (pintype "passive"))
      (node (ref "R49") (pin "2") (pinfunction "2_2") (pintype "passive"))
      (node (ref "RN3") (pin "2") (pinfunction "2_2") (pintype "passive"))
      (node (ref "RN4") (pin "8") (pinfunction "1_8") (pintype "passive"))
      (node (ref "X5") (pin "8") (pinfunction "8_8") (pintype "passive"))
    )
    (net (code "91") (name "Net-(RN4H-2)") (class "Default")
      (node (ref "R34") (pin "1") (pinfunction "1_1") (pintype "passive"))
      (node (ref "RN4") (pin "9") (pinfunction "2_9") (pintype "passive"))
      (node (ref "U4") (pin "2") (pinfunction "A_2") (pintype "input"))
    )
    (net (code "92") (name "Net-(SJ1-1)") (class "Default")
      (node (ref "G1") (pin "PB14") (pinfunction "PB14_PB14") (pintype "bidirectional"))
      (node (ref "SJ1") (pin "P$1") (pinfunction "1_P$1") (pintype "passive"))
    )
    (net (code "93") (name "Net-(SJ2-2)") (class "Default")
      (node (ref "G1") (pin "PB13") (pinfunction "PB13_PB13") (pintype "bidirectional"))
      (node (ref "SJ2") (pin "P$2") (pinfunction "2_P$2") (pintype "passive"))
    )
    (net (code "94") (name "Net-(SJ3-1)") (class "Default")
      (node (ref "G1") (pin "VIN2") (pinfunction "VIN2_VIN2") (pintype "power_in"))
      (node (ref "SJ3") (pin "P$1") (pinfunction "1_P$1") (pintype "passive"))
    )
    (net (code "95") (name "Net-(SJ5-2)") (class "Default")
      (node (ref "JP5") (pin "2") (pinfunction "2_2") (pintype "passive"))
      (node (ref "SJ4") (pin "2") (pinfunction "2_2") (pintype "passive"))
      (node (ref "SJ5") (pin "P$2") (pinfunction "2_P$2") (pintype "passive"))
    )
    (net (code "96") (name "Net-(SJ6-2)") (class "Default")
      (node (ref "SJ6") (pin "P$2") (pinfunction "2_P$2") (pintype "passive"))
      (node (ref "U1") (pin "5") (pinfunction "VREF_5") (pintype "output"))
      (node (ref "U1B") (pin "5") (pinfunction "VREF_5") (pintype "bidirectional"))
    )
    (net (code "97") (name "Net-(SJ10-1)") (class "Default")
      (node (ref "SJ10") (pin "P$1") (pinfunction "1_P$1") (pintype "passive"))
      (node (ref "SJ12") (pin "1") (pinfunction "1_1") (pintype "passive"))
      (node (ref "SJ8") (pin "P$1") (pinfunction "1_P$1") (pintype "passive"))
      (node (ref "U12") (pin "9") (pinfunction "GND_9") (pintype "power_in"))
    )
    (net (code "98") (name "Net-(SJ11-1)") (class "Default")
      (node (ref "SJ11") (pin "P$1") (pinfunction "1_P$1") (pintype "passive"))
      (node (ref "SJ13") (pin "P$1") (pinfunction "1_P$1") (pintype "passive"))
      (node (ref "SJ9") (pin "P$1") (pinfunction "1_P$1") (pintype "passive"))
      (node (ref "U12") (pin "10") (pinfunction "CD+_10") (pintype "passive"))
      (node (ref "X8") (pin "9") (pinfunction "9_9") (pintype "passive"))
    )
    (net (code "99") (name "Net-(SJ15-1)") (class "Default")
      (node (ref "SJ15") (pin "P$1") (pinfunction "1_P$1") (pintype "passive"))
      (node (ref "SJ17") (pin "P$1") (pinfunction "1_P$1") (pintype "passive"))
      (node (ref "SJ19") (pin "1") (pinfunction "1_1") (pintype "passive"))
      (node (ref "U14") (pin "9") (pinfunction "GND_9") (pintype "power_in"))
    )
    (net (code "100") (name "Net-(SJ16-1)") (class "Default")
      (node (ref "SJ16") (pin "P$1") (pinfunction "1_P$1") (pintype "passive"))
      (node (ref "SJ18") (pin "P$1") (pinfunction "1_P$1") (pintype "passive"))
      (node (ref "SJ20") (pin "P$1") (pinfunction "1_P$1") (pintype "passive"))
      (node (ref "U14") (pin "10") (pinfunction "CD+_10") (pintype "passive"))
      (node (ref "X9") (pin "9") (pinfunction "9_9") (pintype "passive"))
    )
    (net (code "101") (name "Net-(U1-RS)") (class "Default")
      (node (ref "R16") (pin "1") (pinfunction "1_1") (pintype "passive"))
      (node (ref "U1") (pin "8") (pinfunction "RS_8") (pintype "input"))
      (node (ref "U1B") (pin "8") (pinfunction "RS_8") (pintype "bidirectional"))
    )
    (net (code "102") (name "Net-(U2-VOUT)") (class "Default")
      (node (ref "D5") (pin "C") (pinfunction "C_C") (pintype "passive"))
      (node (ref "D6") (pin "C") (pinfunction "C_C") (pintype "passive"))
      (node (ref "L1") (pin "2") (pinfunction "2_2") (pintype "passive"))
      (node (ref "U2") (pin "2") (pinfunction "VOUT_2") (pintype "bidirectional"))
      (node (ref "U2B") (pin "7") (pinfunction "OUT_7") (pintype "passive"))
    )
    (net (code "103") (name "Net-(U5A-O)") (class "Default")
      (node (ref "JP10") (pin "10") (pinfunction "10_10") (pintype "passive"))
      (node (ref "U5") (pin "7") (pinfunction "O_7") (pintype "output"))
      (node (ref "U6") (pin "7") (pinfunction "OUT_7") (pintype "output"))
      (node (ref "X7") (pin "1") (pinfunction "1_1") (pintype "passive"))
    )
    (net (code "104") (name "Net-(U5B-O)") (class "Default")
      (node (ref "JP10") (pin "9") (pinfunction "9_9") (pintype "passive"))
      (node (ref "U5") (pin "5") (pinfunction "O_5") (pintype "output"))
      (node (ref "U6") (pin "8") (pinfunction "OUT_8") (pintype "output"))
      (node (ref "X7") (pin "2") (pinfunction "2_2") (pintype "passive"))
    )
    (net (code "105") (name "Net-(U6A--IN)") (class "Default")
      (node (ref "R50") (pin "1") (pinfunction "1_1") (pintype "passive"))
      (node (ref "R51") (pin "2") (pinfunction "2_2") (pintype "passive"))
      (node (ref "U6") (pin "13") (pinfunction "-IN_13") (pintype "input"))
      (node (ref "U6") (pin "2") (pinfunction "-IN_2") (pintype "input"))
      (node (ref "U6") (pin "6") (pinfunction "-IN_6") (pintype "input"))
      (node (ref "U6") (pin "9") (pinfunction "-IN_9") (pintype "input"))
      (node (ref "U9") (pin "13") (pinfunction "-IN_13") (pintype "input"))
      (node (ref "U9") (pin "2") (pinfunction "-IN_2") (pintype "input"))
      (node (ref "U9") (pin "6") (pinfunction "-IN_6") (pintype "input"))
      (node (ref "U9") (pin "9") (pinfunction "-IN_9") (pintype "input"))
    )
    (net (code "106") (name "Net-(U6A-OUT)") (class "Default")
      (node (ref "JP10") (pin "8") (pinfunction "8_8") (pintype "passive"))
      (node (ref "U6") (pin "1") (pinfunction "OUT_1") (pintype "output"))
      (node (ref "U7") (pin "5") (pinfunction "O_5") (pintype "output"))
      (node (ref "X7") (pin "3") (pinfunction "3_3") (pintype "passive"))
    )
    (net (code "107") (name "Net-(U6D-OUT)") (class "Default")
      (node (ref "JP10") (pin "7") (pinfunction "7_7") (pintype "passive"))
      (node (ref "U6") (pin "14") (pinfunction "OUT_14") (pintype "output"))
      (node (ref "U7") (pin "7") (pinfunction "O_7") (pintype "output"))
      (node (ref "X7") (pin "4") (pinfunction "4_4") (pintype "passive"))
    )
    (net (code "108") (name "Net-(U8A-O)") (class "Default")
      (node (ref "JP10") (pin "4") (pinfunction "4_4") (pintype "passive"))
      (node (ref "U8") (pin "7") (pinfunction "O_7") (pintype "output"))
      (node (ref "U9") (pin "7") (pinfunction "OUT_7") (pintype "output"))
      (node (ref "X7") (pin "5") (pinfunction "5_5") (pintype "passive"))
    )
    (net (code "109") (name "Net-(U8B-O)") (class "Default")
      (node (ref "JP10") (pin "3") (pinfunction "3_3") (pintype "passive"))
      (node (ref "U8") (pin "5") (pinfunction "O_5") (pintype "output"))
      (node (ref "U9") (pin "8") (pinfunction "OUT_8") (pintype "output"))
      (node (ref "X7") (pin "6") (pinfunction "6_6") (pintype "passive"))
    )
    (net (code "110") (name "Net-(U10A-O)") (class "Default")
      (node (ref "JP10") (pin "1") (pinfunction "1_1") (pintype "passive"))
      (node (ref "U10") (pin "7") (pinfunction "O_7") (pintype "output"))
      (node (ref "U9") (pin "14") (pinfunction "OUT_14") (pintype "output"))
      (node (ref "X7") (pin "8") (pinfunction "8_8") (pintype "passive"))
    )
    (net (code "111") (name "Net-(U10B-O)") (class "Default")
      (node (ref "JP10") (pin "2") (pinfunction "2_2") (pintype "passive"))
      (node (ref "U10") (pin "5") (pinfunction "O_5") (pintype "output"))
      (node (ref "U9") (pin "1") (pinfunction "OUT_1") (pintype "output"))
      (node (ref "X7") (pin "7") (pinfunction "7_7") (pintype "passive"))
    )
    (net (code "112") (name "Net-(U11A-QA)") (class "Default")
      (node (ref "R59") (pin "1") (pinfunction "1_1") (pintype "passive"))
      (node (ref "U11") (pin "15") (pinfunction "QA_15") (pintype "tri_state"))
      (node (ref "U12") (pin "1") (pinfunction "I1_1") (pintype "input"))
    )
    (net (code "113") (name "Net-(U11A-QB)") (class "Default")
      (node (ref "R58") (pin "1") (pinfunction "1_1") (pintype "passive"))
      (node (ref "U11") (pin "1") (pinfunction "QB_1") (pintype "tri_state"))
      (node (ref "U12") (pin "2") (pinfunction "I2_2") (pintype "input"))
    )
    (net (code "114") (name "Net-(U11A-QC)") (class "Default")
      (node (ref "R57") (pin "1") (pinfunction "1_1") (pintype "passive"))
      (node (ref "U11") (pin "2") (pinfunction "QC_2") (pintype "tri_state"))
      (node (ref "U12") (pin "3") (pinfunction "I3_3") (pintype "input"))
    )
    (net (code "115") (name "Net-(U11A-QD)") (class "Default")
      (node (ref "R56") (pin "1") (pinfunction "1_1") (pintype "passive"))
      (node (ref "U11") (pin "3") (pinfunction "QD_3") (pintype "tri_state"))
      (node (ref "U12") (pin "4") (pinfunction "I4_4") (pintype "input"))
    )
    (net (code "116") (name "Net-(U11A-QE)") (class "Default")
      (node (ref "R55") (pin "1") (pinfunction "1_1") (pintype "passive"))
      (node (ref "U11") (pin "4") (pinfunction "QE_4") (pintype "tri_state"))
      (node (ref "U12") (pin "5") (pinfunction "I5_5") (pintype "input"))
    )
    (net (code "117") (name "Net-(U11A-QF)") (class "Default")
      (node (ref "R54") (pin "1") (pinfunction "1_1") (pintype "passive"))
      (node (ref "U11") (pin "5") (pinfunction "QF_5") (pintype "tri_state"))
      (node (ref "U12") (pin "6") (pinfunction "I6_6") (pintype "input"))
    )
    (net (code "118") (name "Net-(U11A-QG)") (class "Default")
      (node (ref "R53") (pin "1") (pinfunction "1_1") (pintype "passive"))
      (node (ref "U11") (pin "6") (pinfunction "QG_6") (pintype "tri_state"))
      (node (ref "U12") (pin "7") (pinfunction "I7_7") (pintype "input"))
    )
    (net (code "119") (name "Net-(U11A-QH)") (class "Default")
      (node (ref "R52") (pin "1") (pinfunction "1_1") (pintype "passive"))
      (node (ref "U11") (pin "7") (pinfunction "QH_7") (pintype "tri_state"))
      (node (ref "U12") (pin "8") (pinfunction "I8_8") (pintype "input"))
    )
    (net (code "120") (name "Net-(U13A-QA)") (class "Default")
      (node (ref "R67") (pin "1") (pinfunction "1_1") (pintype "passive"))
      (node (ref "U13") (pin "15") (pinfunction "QA_15") (pintype "tri_state"))
      (node (ref "U14") (pin "1") (pinfunction "I1_1") (pintype "input"))
    )
    (net (code "121") (name "Net-(U13A-QB)") (class "Default")
      (node (ref "R66") (pin "1") (pinfunction "1_1") (pintype "passive"))
      (node (ref "U13") (pin "1") (pinfunction "QB_1") (pintype "tri_state"))
      (node (ref "U14") (pin "2") (pinfunction "I2_2") (pintype "input"))
    )
    (net (code "122") (name "Net-(U13A-QC)") (class "Default")
      (node (ref "R65") (pin "1") (pinfunction "1_1") (pintype "passive"))
      (node (ref "U13") (pin "2") (pinfunction "QC_2") (pintype "tri_state"))
      (node (ref "U14") (pin "3") (pinfunction "I3_3") (pintype "input"))
    )
    (net (code "123") (name "Net-(U13A-QD)") (class "Default")
      (node (ref "R64") (pin "1") (pinfunction "1_1") (pintype "passive"))
      (node (ref "U13") (pin "3") (pinfunction "QD_3") (pintype "tri_state"))
      (node (ref "U14") (pin "4") (pinfunction "I4_4") (pintype "input"))
    )
    (net (code "124") (name "Net-(U13A-QE)") (class "Default")
      (node (ref "R63") (pin "1") (pinfunction "1_1") (pintype "passive"))
      (node (ref "U13") (pin "4") (pinfunction "QE_4") (pintype "tri_state"))
      (node (ref "U14") (pin "5") (pinfunction "I5_5") (pintype "input"))
    )
    (net (code "125") (name "Net-(U13A-QF)") (class "Default")
      (node (ref "R62") (pin "1") (pinfunction "1_1") (pintype "passive"))
      (node (ref "U13") (pin "5") (pinfunction "QF_5") (pintype "tri_state"))
      (node (ref "U14") (pin "6") (pinfunction "I6_6") (pintype "input"))
    )
    (net (code "126") (name "Net-(U13A-QG)") (class "Default")
      (node (ref "R61") (pin "1") (pinfunction "1_1") (pintype "passive"))
      (node (ref "U13") (pin "6") (pinfunction "QG_6") (pintype "tri_state"))
      (node (ref "U14") (pin "7") (pinfunction "I7_7") (pintype "input"))
    )
    (net (code "127") (name "Net-(U13A-QH)") (class "Default")
      (node (ref "R60") (pin "1") (pinfunction "1_1") (pintype "passive"))
      (node (ref "U13") (pin "7") (pinfunction "QH_7") (pintype "tri_state"))
      (node (ref "U14") (pin "8") (pinfunction "I8_8") (pintype "input"))
    )
    (net (code "128") (name "Net-(X1-Pad4)") (class "Default")
      (node (ref "X1") (pin "4") (pinfunction "4_4") (pintype "passive"))
      (node (ref "X2") (pin "4") (pinfunction "4_4") (pintype "passive"))
    )
    (net (code "129") (name "Net-(X1-Pad5)") (class "Default")
      (node (ref "X1") (pin "5") (pinfunction "5_5") (pintype "passive"))
      (node (ref "X2") (pin "5") (pinfunction "5_5") (pintype "passive"))
    )
    (net (code "130") (name "OLAT") (class "Default")
      (node (ref "G1") (pin "PA8") (pinfunction "PA8_PA8") (pintype "bidirectional"))
      (node (ref "R3") (pin "1") (pinfunction "1_1") (pintype "passive"))
      (node (ref "U11") (pin "12") (pinfunction "RCK_12") (pintype "input"))
      (node (ref "U13") (pin "12") (pinfunction "RCK_12") (pintype "input"))
    )
    (net (code "131") (name "SCK") (class "Default")
      (node (ref "G1") (pin "PB3") (pinfunction "PB3_PB3") (pintype "bidirectional"))
      (node (ref "JP5") (pin "3") (pinfunction "3_3") (pintype "passive"))
      (node (ref "R5") (pin "1") (pinfunction "1_1") (pintype "passive"))
      (node (ref "U11") (pin "11") (pinfunction "SCK_11") (pintype "input"))
      (node (ref "U13") (pin "11") (pinfunction "SCK_11") (pintype "input"))
    )
    (net (code "132") (name "SCK2") (class "Default")
      (node (ref "G1") (pin "PB10") (pinfunction "PB10_PB10") (pintype "bidirectional"))
      (node (ref "SJ2") (pin "P$1") (pinfunction "1_P$1") (pintype "passive"))
      (node (ref "U3") (pin "7") (pinfunction "CLK_7") (pintype "input"))
      (node (ref "U4") (pin "7") (pinfunction "CLK_7") (pintype "input"))
    )
    (net (code "133") (name "SLNK1") (class "Default")
      (node (ref "SJ14") (pin "P$1") (pinfunction "1_P$1") (pintype "passive"))
      (node (ref "U11") (pin "14") (pinfunction "SER_14") (pintype "input"))
      (node (ref "U13") (pin "9") (pinfunction "QH*_9") (pintype "tri_state"))
    )
    (net (code "134") (name "SLNK2") (class "Default")
      (node (ref "SJ5") (pin "P$1") (pinfunction "1_P$1") (pintype "passive"))
      (node (ref "U11") (pin "9") (pinfunction "QH*_9") (pintype "tri_state"))
    )
    (net (code "135") (name "SLNK3") (class "Default")
      (node (ref "SJ7") (pin "P$1") (pinfunction "1_P$1") (pintype "passive"))
      (node (ref "U3") (pin "1") (pinfunction "SER_1") (pintype "input"))
      (node (ref "U4") (pin "13") (pinfunction "QH_13") (pintype "output"))
    )
    (net (code "136") (name "SRV1") (class "Default")
      (node (ref "G1") (pin "PC9") (pinfunction "PC9_PC9") (pintype "bidirectional"))
      (node (ref "JP4") (pin "2") (pinfunction "2_2") (pintype "passive"))
      (node (ref "R13") (pin "2") (pinfunction "2_2") (pintype "passive"))
    )
    (net (code "137") (name "SRV2") (class "Default")
      (node (ref "G1") (pin "PC7") (pinfunction "PC7_PC7") (pintype "bidirectional"))
      (node (ref "JP4") (pin "1") (pinfunction "1_1") (pintype "passive"))
      (node (ref "R12") (pin "2") (pinfunction "2_2") (pintype "passive"))
    )
    (net (code "138") (name "SRV3") (class "Default")
      (node (ref "G1") (pin "PC8") (pinfunction "PC8_PC8") (pintype "bidirectional"))
      (node (ref "JP3") (pin "2") (pinfunction "2_2") (pintype "passive"))
      (node (ref "R11") (pin "2") (pinfunction "2_2") (pintype "passive"))
    )
    (net (code "139") (name "SRV4") (class "Default")
      (node (ref "G1") (pin "PC6") (pinfunction "PC6_PC6") (pintype "bidirectional"))
      (node (ref "JP3") (pin "1") (pinfunction "1_1") (pintype "passive"))
      (node (ref "R10") (pin "2") (pinfunction "2_2") (pintype "passive"))
    )
    (net (code "140") (name "SRV5") (class "Default")
      (node (ref "G1") (pin "PC12") (pinfunction "PC12_PC12") (pintype "bidirectional"))
      (node (ref "JP2") (pin "2") (pinfunction "2_2") (pintype "passive"))
      (node (ref "R9") (pin "2") (pinfunction "2_2") (pintype "passive"))
    )
    (net (code "141") (name "SRV6") (class "Default")
      (node (ref "G1") (pin "PA15") (pinfunction "PA15_PA15") (pintype "bidirectional"))
      (node (ref "JP2") (pin "1") (pinfunction "1_1") (pintype "passive"))
      (node (ref "R8") (pin "2") (pinfunction "2_2") (pintype "passive"))
    )
    (net (code "142") (name "SRV7") (class "Default")
      (node (ref "G1") (pin "PF1-PH1") (pinfunction "PF1-PH1_PF1-PH1") (pintype "bidirectional"))
      (node (ref "JP1") (pin "2") (pinfunction "2_2") (pintype "passive"))
      (node (ref "R7") (pin "2") (pinfunction "2_2") (pintype "passive"))
    )
    (net (code "143") (name "SRV8") (class "Default")
      (node (ref "G1") (pin "PD2") (pinfunction "PD2_PD2") (pintype "bidirectional"))
      (node (ref "JP1") (pin "1") (pinfunction "1_1") (pintype "passive"))
      (node (ref "R6") (pin "2") (pinfunction "2_2") (pintype "passive"))
    )
    (net (code "144") (name "TDRV1") (class "Default")
      (node (ref "G1") (pin "PB12") (pinfunction "PB12_PB12") (pintype "bidirectional"))
      (node (ref "U10") (pin "2") (pinfunction "I_2") (pintype "input"))
      (node (ref "U9") (pin "12") (pinfunction "+IN_12") (pintype "input"))
    )
    (net (code "145") (name "TDRV2") (class "Default")
      (node (ref "G1") (pin "PB2") (pinfunction "PB2_PB2") (pintype "bidirectional"))
      (node (ref "U10") (pin "4") (pinfunction "I_4") (pintype "input"))
      (node (ref "U9") (pin "3") (pinfunction "+IN_3") (pintype "input"))
    )
    (net (code "146") (name "TDRV3") (class "Default")
      (node (ref "G1") (pin "PB15") (pinfunction "PB15_PB15") (pintype "bidirectional"))
      (node (ref "U8") (pin "4") (pinfunction "I_4") (pintype "input"))
      (node (ref "U9") (pin "10") (pinfunction "+IN_10") (pintype "input"))
    )
    (net (code "147") (name "TDRV4") (class "Default")
      (node (ref "G1") (pin "PB1") (pinfunction "PB1_PB1") (pintype "bidirectional"))
      (node (ref "U8") (pin "2") (pinfunction "I_2") (pintype "input"))
      (node (ref "U9") (pin "5") (pinfunction "+IN_5") (pintype "input"))
    )
    (net (code "148") (name "TDRV5") (class "Default")
      (node (ref "G1") (pin "PA0") (pinfunction "PA0_PA0") (pintype "bidirectional"))
      (node (ref "U6") (pin "12") (pinfunction "+IN_12") (pintype "input"))
      (node (ref "U7") (pin "2") (pinfunction "I_2") (pintype "input"))
    )
    (net (code "149") (name "TDRV6") (class "Default")
      (node (ref "G1") (pin "PA4") (pinfunction "PA4_PA4") (pintype "bidirectional"))
      (node (ref "U6") (pin "3") (pinfunction "+IN_3") (pintype "input"))
      (node (ref "U7") (pin "4") (pinfunction "I_4") (pintype "input"))
    )
    (net (code "150") (name "TDRV7") (class "Default")
      (node (ref "G1") (pin "PC3") (pinfunction "PC3_PC3") (pintype "bidirectional"))
      (node (ref "U5") (pin "4") (pinfunction "I_4") (pintype "input"))
      (node (ref "U6") (pin "10") (pinfunction "+IN_10") (pintype "input"))
    )
    (net (code "151") (name "TDRV8") (class "Default")
      (node (ref "G1") (pin "PC0") (pinfunction "PC0_PC0") (pintype "bidirectional"))
      (node (ref "U5") (pin "2") (pinfunction "I_2") (pintype "input"))
      (node (ref "U6") (pin "5") (pinfunction "+IN_5") (pintype "input"))
    )
    (net (code "152") (name "V+") (class "Default")
      (node (ref "C6") (pin "+") (pinfunction "+_+") (pintype "passive"))
      (node (ref "C7") (pin "1") (pinfunction "1_1") (pintype "passive"))
      (node (ref "G1") (pin "E5V") (pinfunction "E5V_E5V") (pintype "power_in"))
      (node (ref "L1") (pin "1") (pinfunction "1_1") (pintype "passive"))
      (node (ref "U2") (pin "3") (pinfunction "FB_3") (pintype "bidirectional"))
      (node (ref "U2B") (pin "1") (pinfunction "FB_1") (pintype "input"))
    )
    (net (code "153") (name "unconnected-(G1-PadBOOT0)") (class "Default")
      (node (ref "G1") (pin "BOOT0") (pinfunction "BOOT0_BOOT0") (pintype "bidirectional"))
    )
    (net (code "154") (name "unconnected-(G1-PadIOREF2)") (class "Default")
      (node (ref "G1") (pin "IOREF2") (pinfunction "IOREF2_IOREF2") (pintype "input"))
    )
    (net (code "155") (name "unconnected-(G1-PadNC1-PF7)") (class "Default")
      (node (ref "G1") (pin "NC1-PF7") (pinfunction "NC1-PF7_NC1-PF7") (pintype "bidirectional"))
    )
    (net (code "156") (name "unconnected-(G1-PadNC2-PF6)") (class "Default")
      (node (ref "G1") (pin "NC2-PF6") (pinfunction "NC2-PF6_NC2-PF6") (pintype "bidirectional"))
    )
    (net (code "157") (name "unconnected-(G1-PadNC3)") (class "Default")
      (node (ref "G1") (pin "NC3") (pinfunction "NC3_NC3") (pintype "no_connect"))
    )
    (net (code "158") (name "unconnected-(G1-PadNC4)") (class "Default")
      (node (ref "G1") (pin "NC4") (pinfunction "NC4_NC4") (pintype "no_connect"))
    )
    (net (code "159") (name "unconnected-(G1-PadNC5-PD8)") (class "Default")
      (node (ref "G1") (pin "NC5-PD8") (pinfunction "NC5-PD8_NC5-PD8") (pintype "bidirectional"))
    )
    (net (code "160") (name "unconnected-(G1-PadNC6-PB11)") (class "Default")
      (node (ref "G1") (pin "NC6-PB11") (pinfunction "NC6-PB11_NC6-PB11") (pintype "no_connect"))
    )
    (net (code "161") (name "unconnected-(G1-PadNC7-PF5)") (class "Default")
      (node (ref "G1") (pin "NC7-PF5") (pinfunction "NC7-PF5_NC7-PF5") (pintype "bidirectional"))
    )
    (net (code "162") (name "unconnected-(G1-PadNC8-PF4)") (class "Default")
      (node (ref "G1") (pin "NC8-PF4") (pinfunction "NC8-PF4_NC8-PF4") (pintype "bidirectional"))
    )
    (net (code "163") (name "unconnected-(G1-PadNRESET)") (class "Default")
      (node (ref "G1") (pin "NRESET") (pinfunction "NRESET_NRESET") (pintype "input"))
    )
    (net (code "164") (name "unconnected-(G1-PadPA1)") (class "Default")
      (node (ref "G1") (pin "PA1") (pinfunction "PA1_PA1") (pintype "bidirectional"))
    )
    (net (code "165") (name "unconnected-(G1-PadPA2)") (class "Default")
      (node (ref "G1") (pin "PA2") (pinfunction "PA2_PA2") (pintype "bidirectional"))
    )
    (net (code "166") (name "unconnected-(G1-PadPA3)") (class "Default")
      (node (ref "G1") (pin "PA3") (pinfunction "PA3_PA3") (pintype "bidirectional"))
    )
    (net (code "167") (name "unconnected-(G1-PadPA5)") (class "Default")
      (node (ref "G1") (pin "PA5") (pinfunction "PA5_PA5") (pintype "bidirectional"))
    )
    (net (code "168") (name "unconnected-(G1-PadPA7)") (class "Default")
      (node (ref "G1") (pin "PA7") (pinfunction "PA7_PA7") (pintype "bidirectional"))
    )
    (net (code "169") (name "unconnected-(G1-PadPA9)") (class "Default")
      (node (ref "G1") (pin "PA9") (pinfunction "PA9_PA9") (pintype "bidirectional"))
    )
    (net (code "170") (name "unconnected-(G1-PadPA10)") (class "Default")
      (node (ref "G1") (pin "PA10") (pinfunction "PA10_PA10") (pintype "bidirectional"))
    )
    (net (code "171") (name "unconnected-(G1-PadPA11)") (class "Default")
      (node (ref "G1") (pin "PA11") (pinfunction "PA11_PA11") (pintype "bidirectional"))
    )
    (net (code "172") (name "unconnected-(G1-PadPA12)") (class "Default")
      (node (ref "G1") (pin "PA12") (pinfunction "PA12_PA12") (pintype "bidirectional"))
    )
    (net (code "173") (name "unconnected-(G1-PadPA13)") (class "Default")
      (node (ref "G1") (pin "PA13") (pinfunction "PA13_PA13") (pintype "bidirectional"))
    )
    (net (code "174") (name "unconnected-(G1-PadPA14)") (class "Default")
      (node (ref "G1") (pin "PA14") (pinfunction "PA14_PA14") (pintype "bidirectional"))
    )
    (net (code "175") (name "unconnected-(G1-PadPB0)") (class "Default")
      (node (ref "G1") (pin "PB0") (pinfunction "PB0_PB0") (pintype "bidirectional"))
    )
    (net (code "176") (name "unconnected-(G1-PadPC1)") (class "Default")
      (node (ref "G1") (pin "PC1") (pinfunction "PC1_PC1") (pintype "bidirectional"))
    )
    (net (code "177") (name "unconnected-(G1-PadPC4)") (class "Default")
      (node (ref "G1") (pin "PC4") (pinfunction "PC4_PC4") (pintype "bidirectional"))
    )
    (net (code "178") (name "unconnected-(G1-PadPC5)") (class "Default")
      (node (ref "G1") (pin "PC5") (pinfunction "PC5_PC5") (pintype "bidirectional"))
    )
    (net (code "179") (name "unconnected-(G1-PadPC13)") (class "Default")
      (node (ref "G1") (pin "PC13") (pinfunction "PC13_PC13") (pintype "bidirectional"))
    )
    (net (code "180") (name "unconnected-(G1-PadPC14)") (class "Default")
      (node (ref "G1") (pin "PC14") (pinfunction "PC14_PC14") (pintype "bidirectional"))
    )
    (net (code "181") (name "unconnected-(G1-PadPC15)") (class "Default")
      (node (ref "G1") (pin "PC15") (pinfunction "PC15_PC15") (pintype "bidirectional"))
    )
    (net (code "182") (name "unconnected-(G1-PadPF0-PH0)") (class "Default")
      (node (ref "G1") (pin "PF0-PH0") (pinfunction "PF0-PH0_PF0-PH0") (pintype "bidirectional"))
    )
    (net (code "183") (name "unconnected-(H1-MOUNT-PadB3,3)") (class "Default")
      (node (ref "H1") (pin "B3,3") (pinfunction "MOUNT_B3,3") (pintype "passive"))
    )
    (net (code "184") (name "unconnected-(H2-MOUNT-PadB3,3)") (class "Default")
      (node (ref "H2") (pin "B3,3") (pinfunction "MOUNT_B3,3") (pintype "passive"))
    )
    (net (code "185") (name "unconnected-(H3-MOUNT-PadB3,3)") (class "Default")
      (node (ref "H3") (pin "B3,3") (pinfunction "MOUNT_B3,3") (pintype "passive"))
    )
    (net (code "186") (name "unconnected-(H4-MOUNT-PadB3,3)") (class "Default")
      (node (ref "H4") (pin "B3,3") (pinfunction "MOUNT_B3,3") (pintype "passive"))
    )
  )
)
